# OBCv4_22.net
KiCad netlist of a schematic drawn in EAGLE
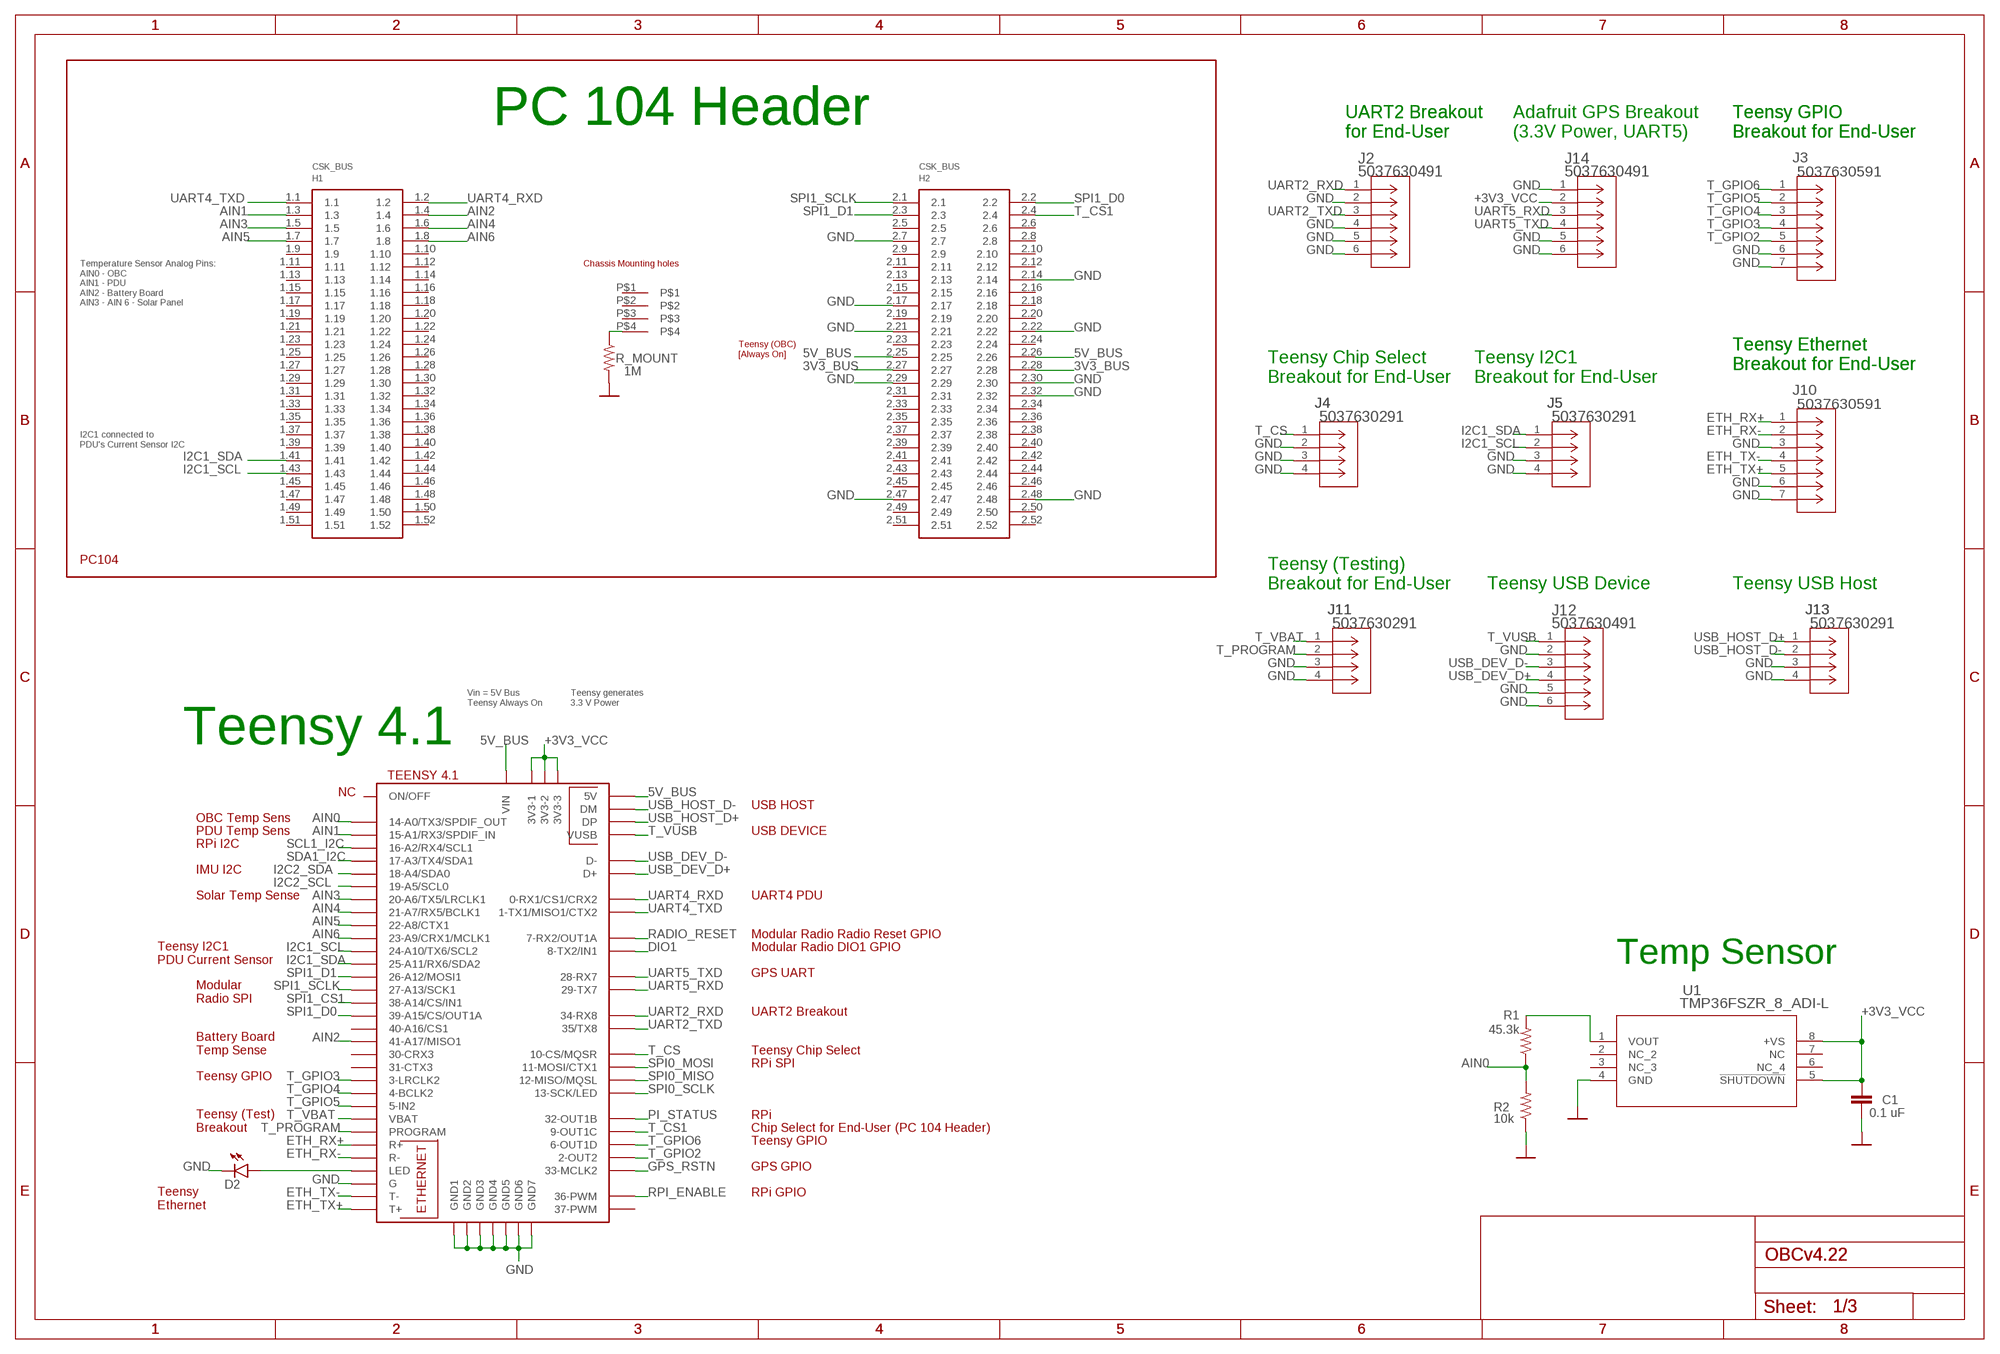
[diagram p0: schematic, sheet 1]
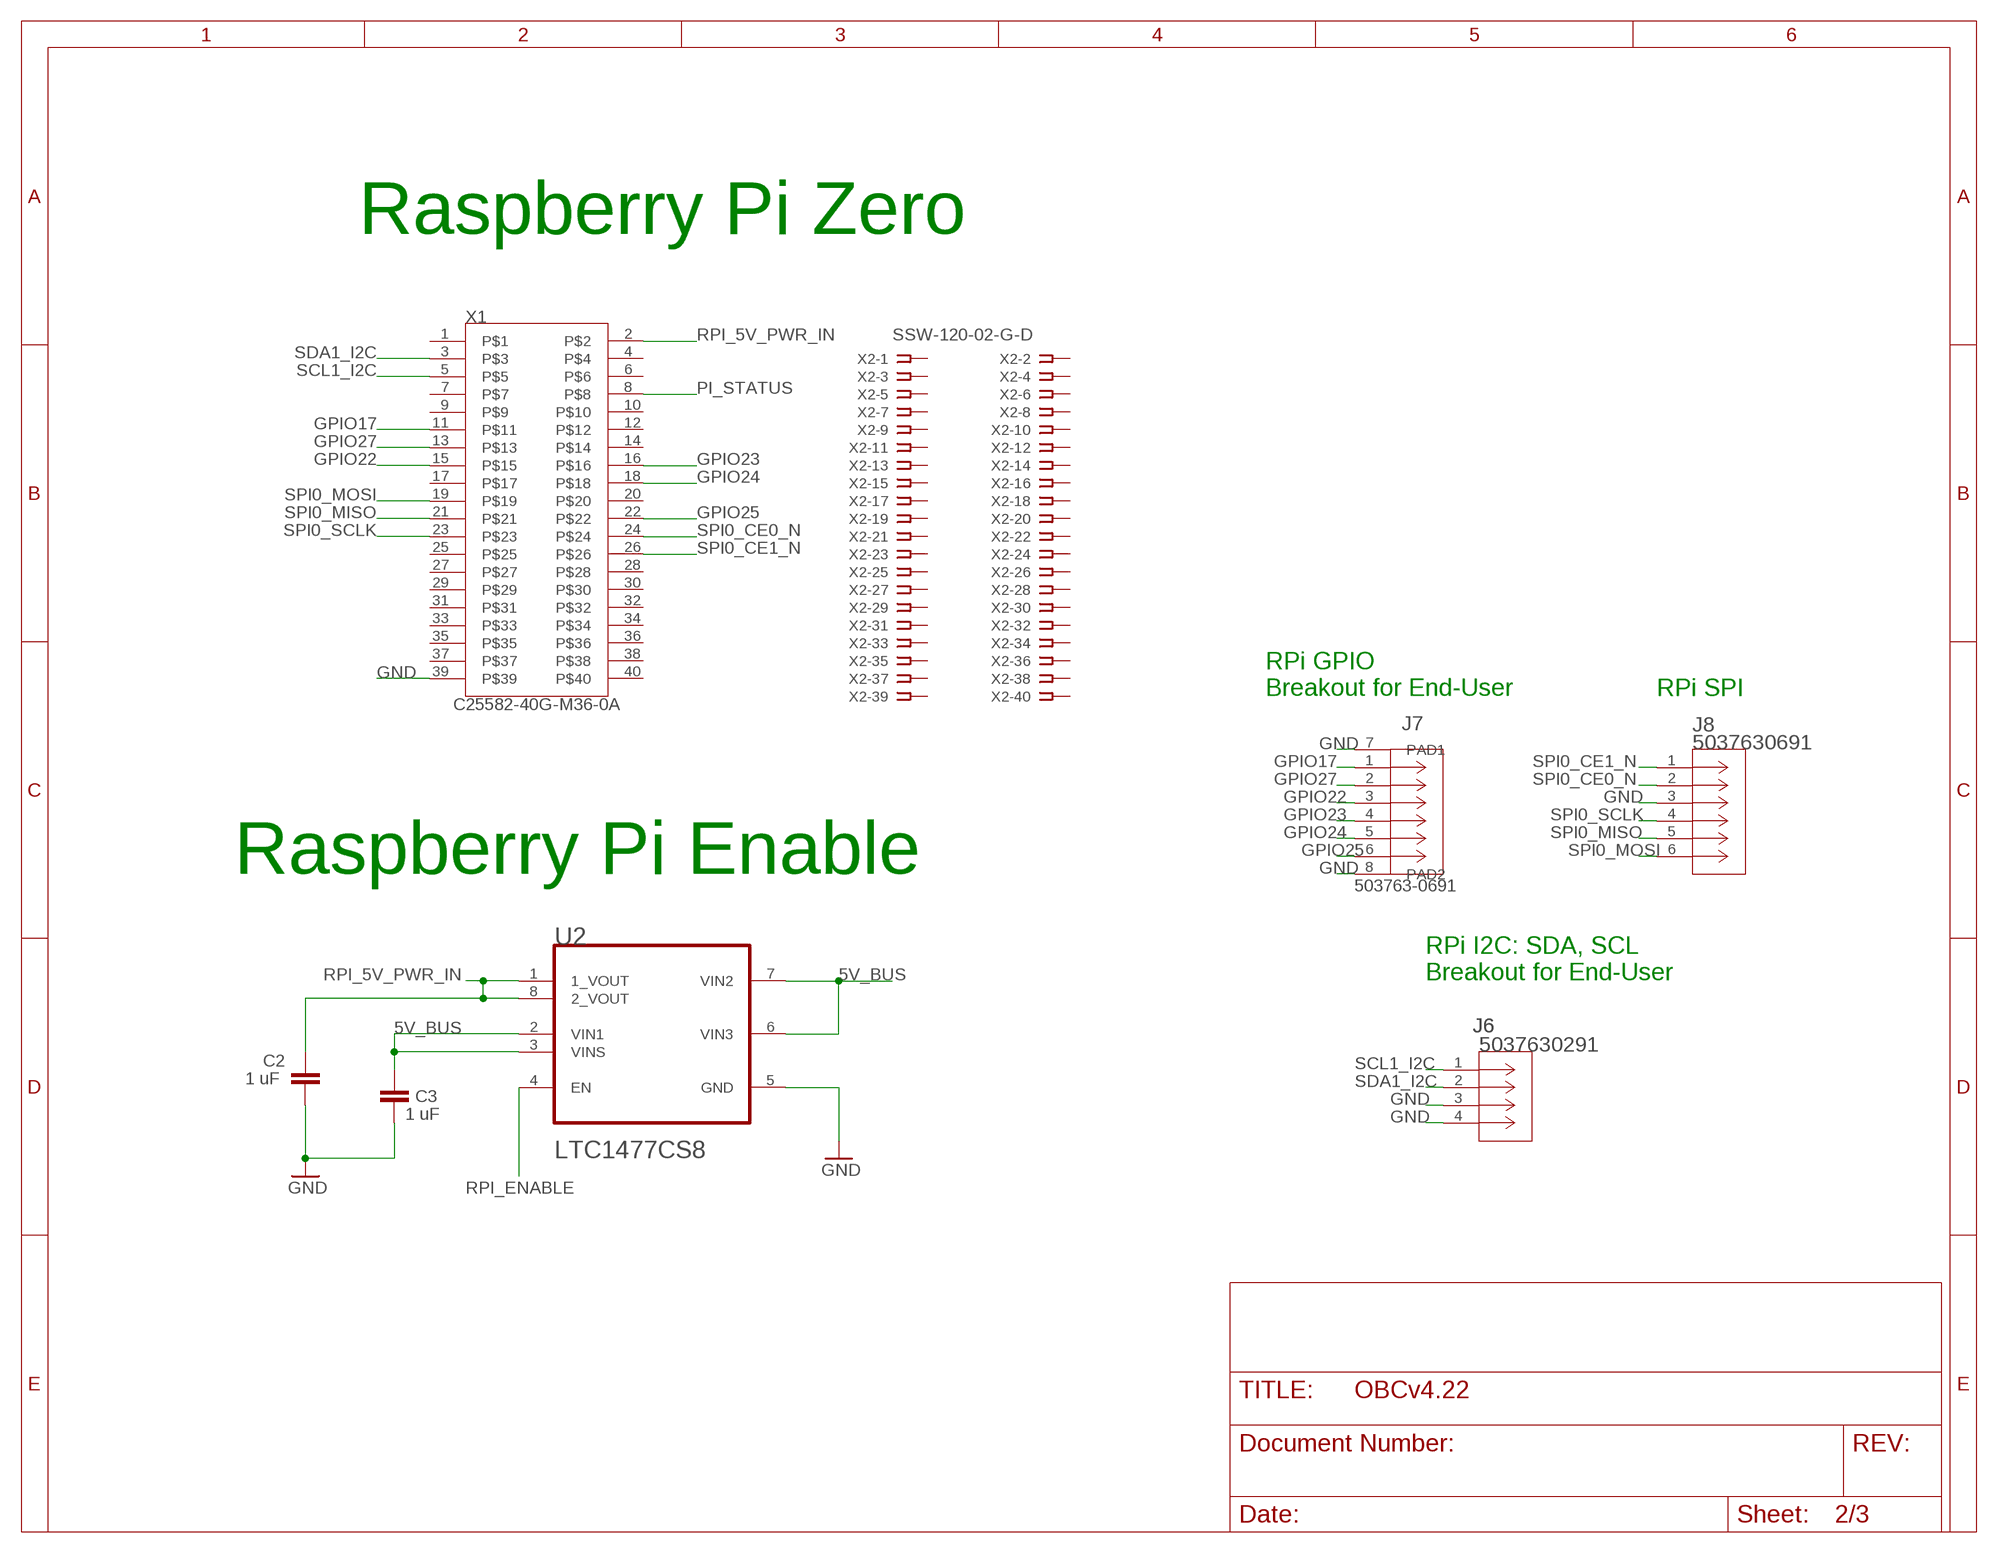
[diagram p1: schematic, sheet 2]
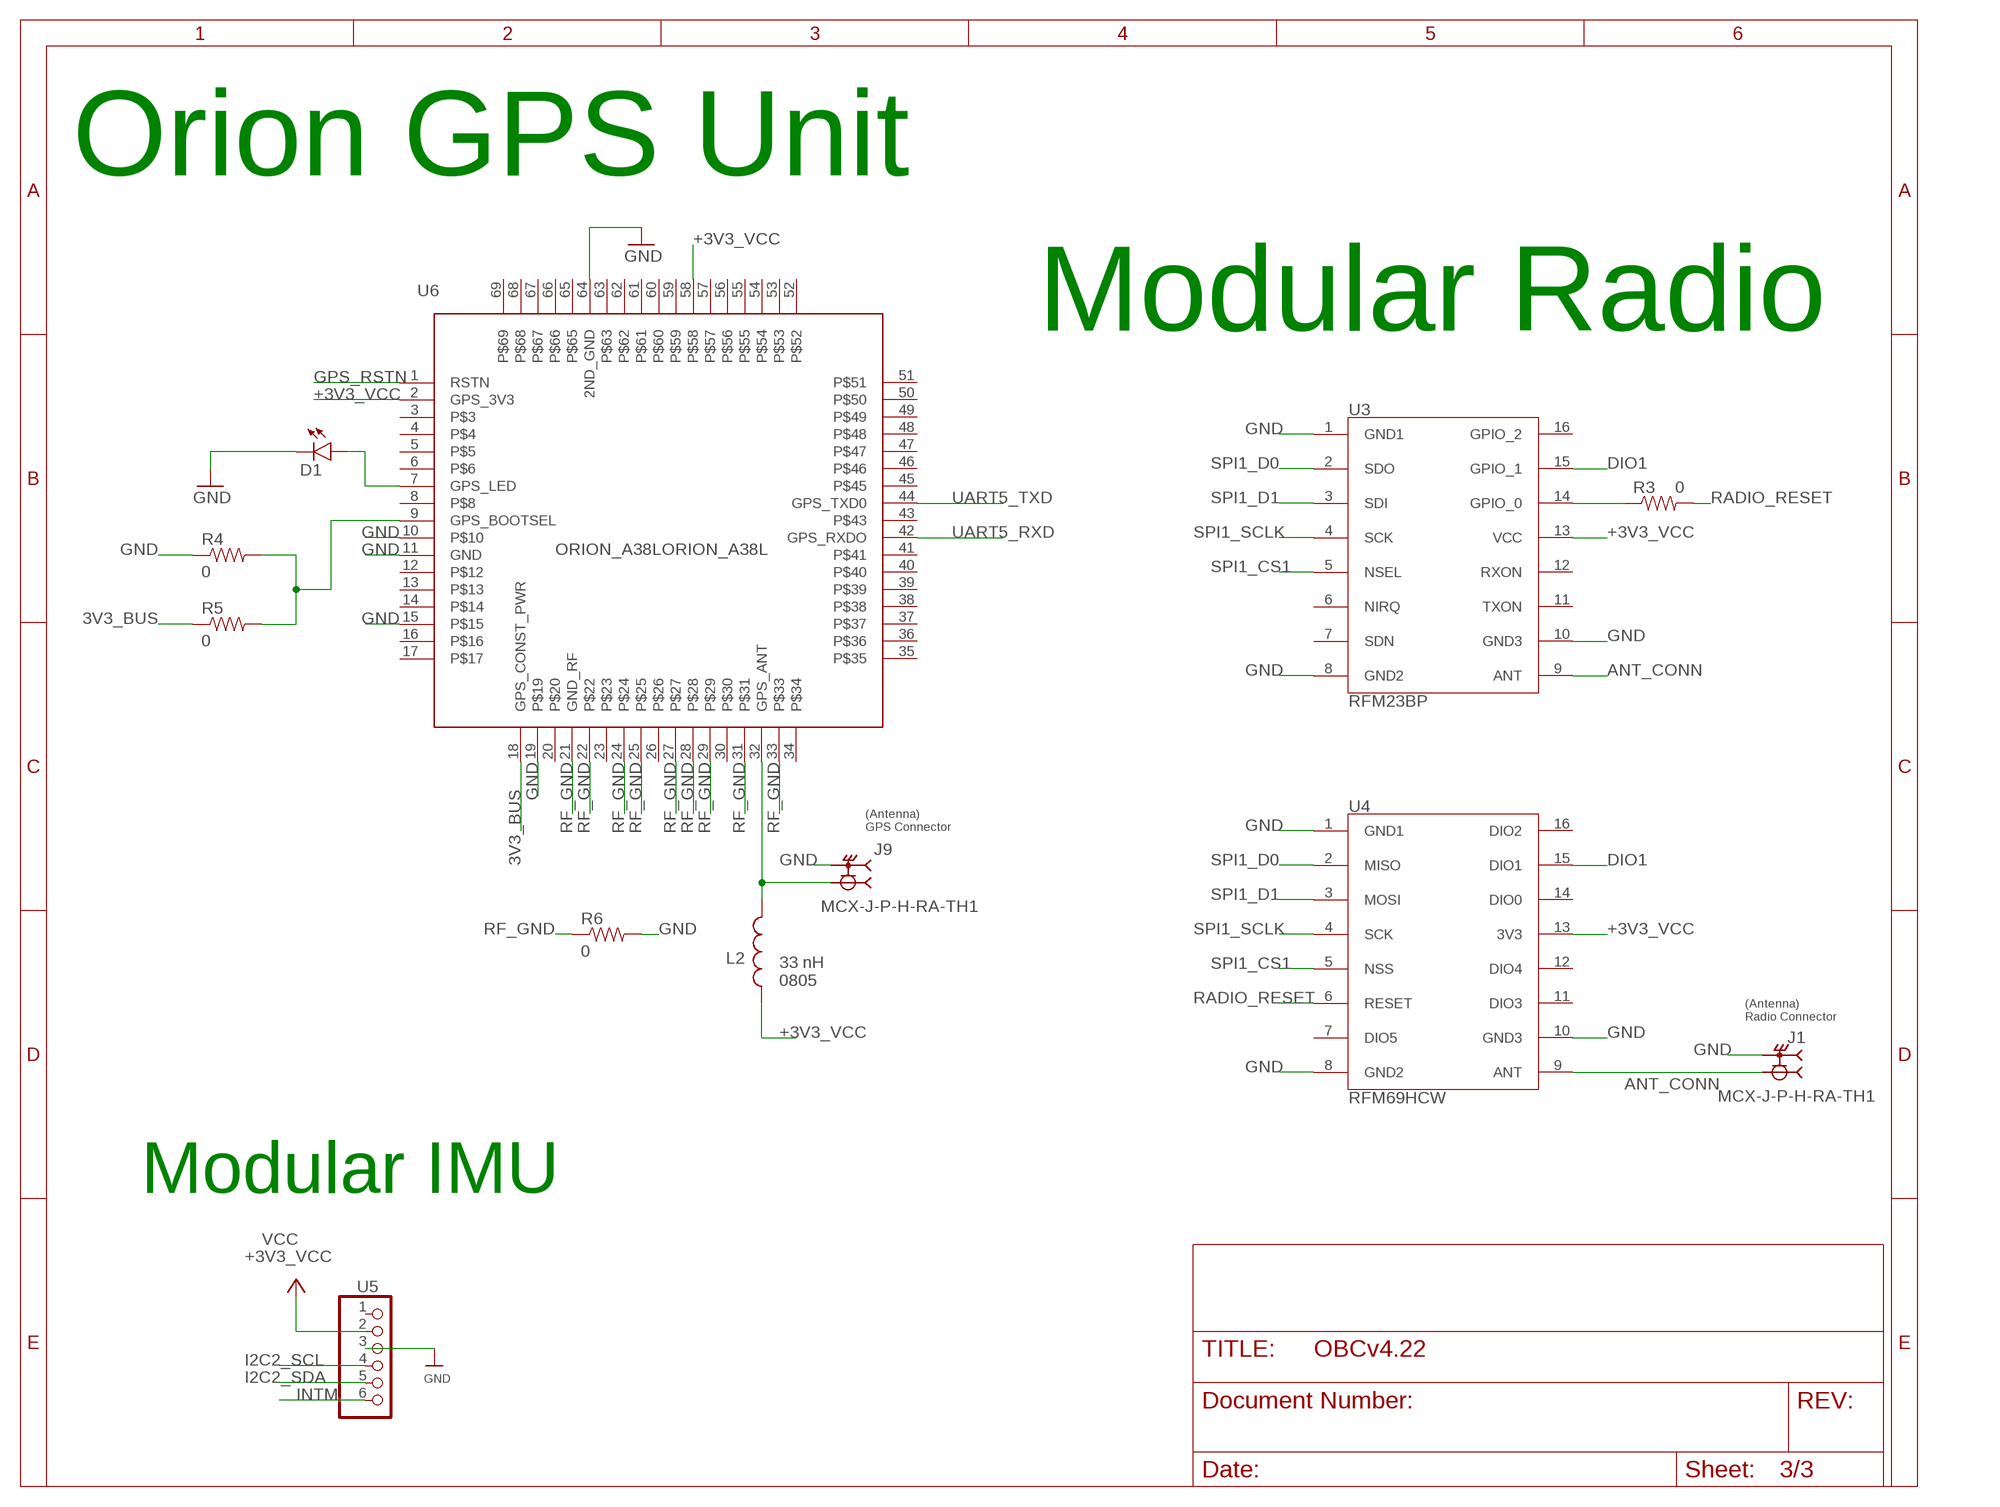
[diagram p2: schematic, sheet 3]

(export (version "E")
  (design (tool "Eeschema 10.0.6"))
  (components
    (comp (ref "C2")
      (value "1 uF")
      (footprint "eagle-import:0805")
      (libsource (lib "eagle-import") (part "CAP0805"))
    )
    (comp (ref "C3")
      (value "1 uF")
      (footprint "eagle-import:0805")
      (libsource (lib "eagle-import") (part "CAP0805"))
    )
    (comp (ref "J6")
      (value "5037630291")
      (footprint "eagle-import:CON_5037630291")
      (fields (field (name "COPYRIGHT") "Copyright (C) 2018 Accelerated Designs. All rights reserved"))
      (libsource (lib "eagle-import") (part "5037630291"))
    )
    (comp (ref "J7")
      (value "503763-0691")
      (footprint "eagle-import:CONN_503763-0691_MOL")
      (fields (field (name "COPYRIGHT") "Copyright (C) 2018 Accelerated Designs. All rights reserved"))
      (libsource (lib "eagle-import") (part "503763-0691"))
    )
    (comp (ref "J8")
      (value "5037630691")
      (footprint "eagle-import:CONN_503763-0691_MOL")
      (fields
        (field (name "MANUFACTURER_PART_NUMBER") "503763-0691")
        (field (name "COPYRIGHT") "Copyright (C) 2018 Accelerated Designs. All rights reserved")
      )
      (libsource (lib "eagle-import") (part "5037630691"))
    )
    (comp (ref "U2")
      (value "LTC1477CS8LINEAR_TECHNOLOGY_LTC1477CS8_0_2")
      (footprint "eagle-import:LINEAR_TECHNOLOGY_LTC1477CS8_2")
      (fields (field (name "MF") "Linear Technology") (field (name "MPN") "LTC1477CS8"))
      (libsource (lib "eagle-import") (part "LTC1477CS8LINEAR_TECHNOLOGY_LTC1477CS8_0_2"))
    )
    (comp (ref "X1")
      (value "C25582-40G-M36-0A")
      (footprint "eagle-import:ADAFRUIT_C25582-40G-M36-0A_0")
      (libsource (lib "eagle-import") (part "C25582-40G-M36-0A"))
    )
    (comp (ref "X2")
      (value "SSW-120-02-G-D")
      (footprint "eagle-import:SSW-120-02-G-D")
      (fields (field (name "MF") "Samtec Inc."))
      (libsource (lib "eagle-import") (part "SSW-120-02-G-D"))
    )
    (comp (ref "D1")
      (value "LEDCHIP-LED0603")
      (footprint "eagle-import:CHIP-LED0603")
      (libsource (lib "eagle-import") (part "LEDCHIP-LED0603"))
    )
    (comp (ref "J1")
      (value "MCX-J-P-H-RA-TH1")
      (footprint "eagle-import:SAMTEC_MCX-J-P-H-RA-TH1")
      (fields (field (name "DIGI-KEY_PART_NUMBER") "SAM10607-ND") (field (name "MF") "Samtec"))
      (libsource (lib "eagle-import") (part "MCX-J-P-H-RA-TH1"))
    )
    (comp (ref "J9")
      (value "MCX-J-P-H-RA-TH1")
      (footprint "eagle-import:SAMTEC_MCX-J-P-H-RA-TH1")
      (fields (field (name "DIGI-KEY_PART_NUMBER") "SAM10607-ND") (field (name "MF") "Samtec"))
      (libsource (lib "eagle-import") (part "MCX-J-P-H-RA-TH1"))
    )
    (comp (ref "L2")
      (value "AIMC-0805-2N2S-T")
      (footprint "eagle-import:INDC2012X105N")
      (fields (field (name "DIGI-KEY_PART_NUMBER") "535-11562-1-ND") (field (name "MF") "Abracon"))
      (libsource (lib "eagle-import") (part "AIMC-0805-2N2S-T"))
    )
    (comp (ref "R3")
      (value "0")
      (footprint "eagle-import:0805")
      (libsource (lib "eagle-import") (part "RESISTOR0805-RES"))
    )
    (comp (ref "R4")
      (value "0")
      (footprint "eagle-import:0805")
      (libsource (lib "eagle-import") (part "RESISTOR0805-RES"))
    )
    (comp (ref "R5")
      (value "0")
      (footprint "eagle-import:0805")
      (libsource (lib "eagle-import") (part "RESISTOR0805-RES"))
    )
    (comp (ref "R6")
      (value "0")
      (footprint "eagle-import:0805")
      (libsource (lib "eagle-import") (part "RESISTOR0805-RES"))
    )
    (comp (ref "U3")
      (value "RFM23BP")
      (footprint "eagle-import:RFM23BP")
      (libsource (lib "eagle-import") (part "RFM23BP"))
    )
    (comp (ref "U4")
      (value "RFM69HCW")
      (footprint "eagle-import:RFM69HCW")
      (libsource (lib "eagle-import") (part "RFM69HCW"))
    )
    (comp (ref "U5")
      (value "HEADER-1X670MIL")
      (footprint "eagle-import:1X06_ROUND_70")
      (libsource (lib "eagle-import") (part "HEADER-1X670MIL"))
    )
    (comp (ref "U6")
      (value "ORION_A38LORION_A38L")
      (footprint "eagle-import:ORION_A38L")
      (libsource (lib "eagle-import") (part "ORION_A38LORION_A38L"))
    )
    (comp (ref "C1")
      (value "0.1 uF")
      (footprint "eagle-import:0805")
      (libsource (lib "eagle-import") (part "CAP0805"))
    )
    (comp (ref "D2")
      (value "LEDCHIP-LED0603")
      (footprint "eagle-import:CHIP-LED0603")
      (libsource (lib "eagle-import") (part "LEDCHIP-LED0603"))
    )
    (comp (ref "H1")
      (value "PC104_WCONN")
      (footprint "eagle-import:PC104_WCONN")
      (libsource (lib "eagle-import") (part "PC104_WCONN"))
    )
    (comp (ref "J2")
      (value "5037630491")
      (footprint "eagle-import:CON_5037630491")
      (fields (field (name "COPYRIGHT") "Copyright (C) 2018 Accelerated Designs. All rights reserved"))
      (libsource (lib "eagle-import") (part "5037630491"))
    )
    (comp (ref "J3")
      (value "5037630591")
      (footprint "eagle-import:CON_5037630591")
      (fields (field (name "COPYRIGHT") "Copyright (C) 2021 Ultra Librarian. All rights reserved."))
      (libsource (lib "eagle-import") (part "5037630591"))
    )
    (comp (ref "J4")
      (value "5037630291")
      (footprint "eagle-import:CON_5037630291")
      (fields (field (name "COPYRIGHT") "Copyright (C) 2018 Accelerated Designs. All rights reserved"))
      (libsource (lib "eagle-import") (part "5037630291"))
    )
    (comp (ref "J5")
      (value "5037630291")
      (footprint "eagle-import:CON_5037630291")
      (fields (field (name "COPYRIGHT") "Copyright (C) 2018 Accelerated Designs. All rights reserved"))
      (libsource (lib "eagle-import") (part "5037630291"))
    )
    (comp (ref "J10")
      (value "5037630591")
      (footprint "eagle-import:CON_5037630591")
      (fields (field (name "COPYRIGHT") "Copyright (C) 2021 Ultra Librarian. All rights reserved."))
      (libsource (lib "eagle-import") (part "5037630591"))
    )
    (comp (ref "J11")
      (value "5037630291")
      (footprint "eagle-import:CON_5037630291")
      (fields (field (name "COPYRIGHT") "Copyright (C) 2018 Accelerated Designs. All rights reserved"))
      (libsource (lib "eagle-import") (part "5037630291"))
    )
    (comp (ref "J12")
      (value "5037630491")
      (footprint "eagle-import:CON_5037630491")
      (fields (field (name "COPYRIGHT") "Copyright (C) 2018 Accelerated Designs. All rights reserved"))
      (libsource (lib "eagle-import") (part "5037630491"))
    )
    (comp (ref "J13")
      (value "5037630291")
      (footprint "eagle-import:CON_5037630291")
      (fields (field (name "COPYRIGHT") "Copyright (C) 2018 Accelerated Designs. All rights reserved"))
      (libsource (lib "eagle-import") (part "5037630291"))
    )
    (comp (ref "J14")
      (value "5037630491")
      (footprint "eagle-import:CON_5037630491")
      (fields (field (name "COPYRIGHT") "Copyright (C) 2018 Accelerated Designs. All rights reserved"))
      (libsource (lib "eagle-import") (part "5037630491"))
    )
    (comp (ref "R1")
      (value "45.3k")
      (footprint "eagle-import:0805")
      (libsource (lib "eagle-import") (part "RESISTOR0805-RES"))
    )
    (comp (ref "R2")
      (value "10k")
      (footprint "eagle-import:0805")
      (libsource (lib "eagle-import") (part "RESISTOR0805-RES"))
    )
    (comp (ref "R_MOUNT")
      (value "1M")
      (footprint "eagle-import:0805")
      (libsource (lib "eagle-import") (part "RESISTOR0805-RES"))
    )
    (comp (ref "U$1")
      (value "TEENSY41TEENSY")
      (footprint "eagle-import:TEENSY41")
      (libsource (lib "eagle-import") (part "TEENSY41TEENSY"))
    )
    (comp (ref "U1")
      (value "TMP36FSZR_8_ADI-L")
      (footprint "eagle-import:R_8_ADI-L")
      (fields
        (field (name "MANUFACTURER_PART_NUMBER") "TMP36FSZ")
        (field (name "COPYRIGHT") "Copyright (C) 2021 Ultra Librarian. All rights reserved.")
      )
      (libsource (lib "eagle-import") (part "TMP36FSZR_8_ADI-L"))
    )
  )
  (nets
    (net (code "1") (name "+3V3_VCC") (class "Default")
      (node (ref "C1") (pin "1") (pinfunction "1_1") (pintype "passive"))
      (node (ref "J14") (pin "2") (pinfunction "2_2") (pintype "passive"))
      (node (ref "L2") (pin "1") (pinfunction "1_1") (pintype "passive"))
      (node (ref "U$1") (pin "3V3-1") (pinfunction "3V3-1_3V3-1") (pintype "bidirectional"))
      (node (ref "U$1") (pin "3V3-2") (pinfunction "3V3-2_3V3-2") (pintype "bidirectional"))
      (node (ref "U$1") (pin "3V3-3") (pinfunction "3V3-3_3V3-3") (pintype "bidirectional"))
      (node (ref "U1") (pin "5") (pinfunction "~{SHUTDOWN}_5") (pintype "passive"))
      (node (ref "U1") (pin "8") (pinfunction "+VS_8") (pintype "power_in"))
      (node (ref "U3") (pin "13") (pinfunction "VCC_13") (pintype "bidirectional"))
      (node (ref "U4") (pin "13") (pinfunction "3V3_13") (pintype "bidirectional"))
      (node (ref "U5") (pin "2") (pinfunction "2_2") (pintype "passive"))
      (node (ref "U6") (pin "2") (pinfunction "GPS_3V3_2") (pintype "bidirectional"))
      (node (ref "U6") (pin "58") (pinfunction "P$58_58") (pintype "bidirectional"))
    )
    (net (code "2") (name "3V3_BUS") (class "Default")
      (node (ref "H1") (pin "2.27") (pinfunction "2.27_2.27") (pintype "bidirectional"))
      (node (ref "H1") (pin "2.28") (pinfunction "2.28_2.28") (pintype "bidirectional"))
      (node (ref "R5") (pin "1") (pinfunction "1_1") (pintype "passive"))
      (node (ref "U6") (pin "18") (pinfunction "GPS_CONST_PWR_18") (pintype "bidirectional"))
    )
    (net (code "3") (name "5V_BUS") (class "Default")
      (node (ref "C3") (pin "1") (pinfunction "1_1") (pintype "passive"))
      (node (ref "H1") (pin "2.25") (pinfunction "2.25_2.25") (pintype "bidirectional"))
      (node (ref "H1") (pin "2.26") (pinfunction "2.26_2.26") (pintype "bidirectional"))
      (node (ref "U$1") (pin "+5V") (pinfunction "5V_+5V") (pintype "bidirectional"))
      (node (ref "U$1") (pin "VIN") (pinfunction "VIN_VIN") (pintype "bidirectional"))
      (node (ref "U2") (pin "2") (pinfunction "VIN1_2") (pintype "power_in"))
      (node (ref "U2") (pin "3") (pinfunction "VINS_3") (pintype "power_in"))
      (node (ref "U2") (pin "6") (pinfunction "VIN3_6") (pintype "power_in"))
      (node (ref "U2") (pin "7") (pinfunction "VIN2_7") (pintype "power_in"))
    )
    (net (code "4") (name "AIN0") (class "Default")
      (node (ref "R1") (pin "1") (pinfunction "1_1") (pintype "passive"))
      (node (ref "R2") (pin "2") (pinfunction "2_2") (pintype "passive"))
      (node (ref "U$1") (pin "14-A0/TX3/SPDIF_OUT") (pinfunction "14-A0/TX3/SPDIF_OUT_14-A0/TX3/SPDIF_OUT") (pintype "bidirectional"))
    )
    (net (code "5") (name "AIN1") (class "Default")
      (node (ref "H1") (pin "1.3") (pinfunction "1.3_1.3") (pintype "bidirectional"))
      (node (ref "U$1") (pin "15-A1/RX3/SPDIF_IN") (pinfunction "15-A1/RX3/SPDIF_IN_15-A1/RX3/SPDIF_IN") (pintype "bidirectional"))
    )
    (net (code "6") (name "AIN2") (class "Default")
      (node (ref "H1") (pin "1.4") (pinfunction "1.4_1.4") (pintype "bidirectional"))
      (node (ref "U$1") (pin "41-A17/MISO1") (pinfunction "41-A17/MISO1_41-A17/MISO1") (pintype "bidirectional"))
    )
    (net (code "7") (name "AIN3") (class "Default")
      (node (ref "H1") (pin "1.5") (pinfunction "1.5_1.5") (pintype "bidirectional"))
      (node (ref "U$1") (pin "20-A6/TX5/LRCLK1") (pinfunction "20-A6/TX5/LRCLK1_20-A6/TX5/LRCLK1") (pintype "bidirectional"))
    )
    (net (code "8") (name "AIN4") (class "Default")
      (node (ref "H1") (pin "1.6") (pinfunction "1.6_1.6") (pintype "bidirectional"))
      (node (ref "U$1") (pin "21-A7/RX5/BCLK1") (pinfunction "21-A7/RX5/BCLK1_21-A7/RX5/BCLK1") (pintype "bidirectional"))
    )
    (net (code "9") (name "AIN5") (class "Default")
      (node (ref "H1") (pin "1.7") (pinfunction "1.7_1.7") (pintype "bidirectional"))
      (node (ref "U$1") (pin "22-A8/CTX1") (pinfunction "22-A8/CTX1_22-A8/CTX1") (pintype "bidirectional"))
    )
    (net (code "10") (name "AIN6") (class "Default")
      (node (ref "H1") (pin "1.8") (pinfunction "1.8_1.8") (pintype "bidirectional"))
      (node (ref "U$1") (pin "23-A9/CRX1/MCLK1") (pinfunction "23-A9/CRX1/MCLK1_23-A9/CRX1/MCLK1") (pintype "bidirectional"))
    )
    (net (code "11") (name "ANT_CONN") (class "Default")
      (node (ref "J1") (pin "1") (pinfunction "1_1") (pintype "passive"))
      (node (ref "U3") (pin "9") (pinfunction "ANT_9") (pintype "bidirectional"))
      (node (ref "U4") (pin "9") (pinfunction "ANT_9") (pintype "bidirectional"))
    )
    (net (code "12") (name "DIO1") (class "Default")
      (node (ref "U$1") (pin "8-TX2/IN1") (pinfunction "8-TX2/IN1_8-TX2/IN1") (pintype "bidirectional"))
      (node (ref "U3") (pin "15") (pinfunction "GPIO_1_15") (pintype "bidirectional"))
      (node (ref "U4") (pin "15") (pinfunction "DIO1_15") (pintype "bidirectional"))
    )
    (net (code "13") (name "ETH_RX+") (class "Default")
      (node (ref "J10") (pin "1") (pinfunction "1_1") (pintype "passive"))
      (node (ref "U$1") (pin "R+") (pinfunction "R+_R+") (pintype "bidirectional"))
    )
    (net (code "14") (name "ETH_RX-") (class "Default")
      (node (ref "J10") (pin "2") (pinfunction "2_2") (pintype "passive"))
      (node (ref "U$1") (pin "R-") (pinfunction "R-_R-") (pintype "bidirectional"))
    )
    (net (code "15") (name "ETH_TX+") (class "Default")
      (node (ref "J10") (pin "5") (pinfunction "5_5") (pintype "passive"))
      (node (ref "U$1") (pin "T+") (pinfunction "T+_T+") (pintype "bidirectional"))
    )
    (net (code "16") (name "ETH_TX-") (class "Default")
      (node (ref "J10") (pin "4") (pinfunction "4_4") (pintype "passive"))
      (node (ref "U$1") (pin "T-") (pinfunction "T-_T-") (pintype "bidirectional"))
    )
    (net (code "17") (name "GND") (class "Default")
      (node (ref "C1") (pin "2") (pinfunction "2_2") (pintype "passive"))
      (node (ref "C2") (pin "2") (pinfunction "2_2") (pintype "passive"))
      (node (ref "C3") (pin "2") (pinfunction "2_2") (pintype "passive"))
      (node (ref "D1") (pin "C") (pinfunction "C_C") (pintype "passive"))
      (node (ref "D2") (pin "C") (pinfunction "C_C") (pintype "passive"))
      (node (ref "H1") (pin "2.14") (pinfunction "2.14_2.14") (pintype "bidirectional"))
      (node (ref "H1") (pin "2.17") (pinfunction "2.17_2.17") (pintype "bidirectional"))
      (node (ref "H1") (pin "2.21") (pinfunction "2.21_2.21") (pintype "bidirectional"))
      (node (ref "H1") (pin "2.22") (pinfunction "2.22_2.22") (pintype "bidirectional"))
      (node (ref "H1") (pin "2.29") (pinfunction "2.29_2.29") (pintype "bidirectional"))
      (node (ref "H1") (pin "2.30") (pinfunction "2.30_2.30") (pintype "bidirectional"))
      (node (ref "H1") (pin "2.32") (pinfunction "2.32_2.32") (pintype "bidirectional"))
      (node (ref "H1") (pin "2.47") (pinfunction "2.47_2.47") (pintype "bidirectional"))
      (node (ref "H1") (pin "2.48") (pinfunction "2.48_2.48") (pintype "bidirectional"))
      (node (ref "H1") (pin "2.7") (pinfunction "2.7_2.7") (pintype "bidirectional"))
      (node (ref "J1") (pin "S1") (pinfunction "2_S1") (pintype "passive"))
      (node (ref "J1") (pin "S2") (pinfunction "2_S2") (pintype "passive"))
      (node (ref "J1") (pin "S3") (pinfunction "2_S3") (pintype "passive"))
      (node (ref "J1") (pin "S4") (pinfunction "2_S4") (pintype "passive"))
      (node (ref "J10") (pin "3") (pinfunction "3_3") (pintype "passive"))
      (node (ref "J10") (pin "6") (pinfunction "6_6") (pintype "passive"))
      (node (ref "J10") (pin "7") (pinfunction "7_7") (pintype "passive"))
      (node (ref "J11") (pin "3") (pinfunction "3_3") (pintype "passive"))
      (node (ref "J11") (pin "4") (pinfunction "4_4") (pintype "passive"))
      (node (ref "J12") (pin "2") (pinfunction "2_2") (pintype "passive"))
      (node (ref "J12") (pin "5") (pinfunction "5_5") (pintype "passive"))
      (node (ref "J12") (pin "6") (pinfunction "6_6") (pintype "passive"))
      (node (ref "J13") (pin "3") (pinfunction "3_3") (pintype "passive"))
      (node (ref "J13") (pin "4") (pinfunction "4_4") (pintype "passive"))
      (node (ref "J14") (pin "1") (pinfunction "1_1") (pintype "passive"))
      (node (ref "J14") (pin "5") (pinfunction "5_5") (pintype "passive"))
      (node (ref "J14") (pin "6") (pinfunction "6_6") (pintype "passive"))
      (node (ref "J2") (pin "2") (pinfunction "2_2") (pintype "passive"))
      (node (ref "J2") (pin "4") (pinfunction "4_4") (pintype "passive"))
      (node (ref "J2") (pin "5") (pinfunction "5_5") (pintype "passive"))
      (node (ref "J2") (pin "6") (pinfunction "6_6") (pintype "passive"))
      (node (ref "J3") (pin "6") (pinfunction "6_6") (pintype "passive"))
      (node (ref "J3") (pin "7") (pinfunction "7_7") (pintype "passive"))
      (node (ref "J4") (pin "2") (pinfunction "2_2") (pintype "passive"))
      (node (ref "J4") (pin "3") (pinfunction "3_3") (pintype "passive"))
      (node (ref "J4") (pin "4") (pinfunction "4_4") (pintype "passive"))
      (node (ref "J5") (pin "3") (pinfunction "3_3") (pintype "passive"))
      (node (ref "J5") (pin "4") (pinfunction "4_4") (pintype "passive"))
      (node (ref "J6") (pin "3") (pinfunction "3_3") (pintype "passive"))
      (node (ref "J6") (pin "4") (pinfunction "4_4") (pintype "passive"))
      (node (ref "J7") (pin "7") (pinfunction "PAD1_7") (pintype "bidirectional"))
      (node (ref "J7") (pin "8") (pinfunction "PAD2_8") (pintype "bidirectional"))
      (node (ref "J8") (pin "3") (pinfunction "3_3") (pintype "passive"))
      (node (ref "J9") (pin "S1") (pinfunction "2_S1") (pintype "passive"))
      (node (ref "J9") (pin "S2") (pinfunction "2_S2") (pintype "passive"))
      (node (ref "J9") (pin "S3") (pinfunction "2_S3") (pintype "passive"))
      (node (ref "J9") (pin "S4") (pinfunction "2_S4") (pintype "passive"))
      (node (ref "R2") (pin "1") (pinfunction "1_1") (pintype "passive"))
      (node (ref "R4") (pin "1") (pinfunction "1_1") (pintype "passive"))
      (node (ref "R6") (pin "2") (pinfunction "2_2") (pintype "passive"))
      (node (ref "R_MOUNT") (pin "2") (pinfunction "2_2") (pintype "passive"))
      (node (ref "U$1") (pin "G") (pinfunction "G_G") (pintype "bidirectional"))
      (node (ref "U$1") (pin "GND") (pinfunction "GND7_GND") (pintype "bidirectional"))
      (node (ref "U$1") (pin "GND1") (pinfunction "GND1_GND1") (pintype "bidirectional"))
      (node (ref "U$1") (pin "GND2") (pinfunction "GND2_GND2") (pintype "bidirectional"))
      (node (ref "U$1") (pin "GND3") (pinfunction "GND3_GND3") (pintype "bidirectional"))
      (node (ref "U$1") (pin "GND4") (pinfunction "GND4_GND4") (pintype "bidirectional"))
      (node (ref "U$1") (pin "GND5") (pinfunction "GND5_GND5") (pintype "bidirectional"))
      (node (ref "U$1") (pin "GND6") (pinfunction "GND6_GND6") (pintype "bidirectional"))
      (node (ref "U1") (pin "4") (pinfunction "GND_4") (pintype "passive"))
      (node (ref "U2") (pin "5") (pinfunction "GND_5") (pintype "power_in"))
      (node (ref "U3") (pin "1") (pinfunction "GND1_1") (pintype "bidirectional"))
      (node (ref "U3") (pin "10") (pinfunction "GND3_10") (pintype "bidirectional"))
      (node (ref "U3") (pin "8") (pinfunction "GND2_8") (pintype "bidirectional"))
      (node (ref "U4") (pin "1") (pinfunction "GND1_1") (pintype "bidirectional"))
      (node (ref "U4") (pin "10") (pinfunction "GND3_10") (pintype "bidirectional"))
      (node (ref "U4") (pin "8") (pinfunction "GND2_8") (pintype "bidirectional"))
      (node (ref "U5") (pin "3") (pinfunction "3_3") (pintype "passive"))
      (node (ref "U6") (pin "10") (pinfunction "P$10_10") (pintype "bidirectional"))
      (node (ref "U6") (pin "11") (pinfunction "GND_11") (pintype "bidirectional"))
      (node (ref "U6") (pin "15") (pinfunction "P$15_15") (pintype "bidirectional"))
      (node (ref "U6") (pin "19") (pinfunction "P$19_19") (pintype "bidirectional"))
      (node (ref "U6") (pin "64") (pinfunction "2ND_GND_64") (pintype "bidirectional"))
      (node (ref "X1") (pin "39") (pinfunction "P$39_39") (pintype "bidirectional"))
    )
    (net (code "18") (name "GPIO17") (class "Default")
      (node (ref "J7") (pin "1") (pinfunction "1_1") (pintype "passive"))
      (node (ref "X1") (pin "11") (pinfunction "P$11_11") (pintype "bidirectional"))
    )
    (net (code "19") (name "GPIO22") (class "Default")
      (node (ref "J7") (pin "3") (pinfunction "3_3") (pintype "passive"))
      (node (ref "X1") (pin "15") (pinfunction "P$15_15") (pintype "bidirectional"))
    )
    (net (code "20") (name "GPIO23") (class "Default")
      (node (ref "J7") (pin "4") (pinfunction "4_4") (pintype "passive"))
      (node (ref "X1") (pin "16") (pinfunction "P$16_16") (pintype "bidirectional"))
    )
    (net (code "21") (name "GPIO24") (class "Default")
      (node (ref "J7") (pin "5") (pinfunction "5_5") (pintype "passive"))
      (node (ref "X1") (pin "18") (pinfunction "P$18_18") (pintype "bidirectional"))
    )
    (net (code "22") (name "GPIO25") (class "Default")
      (node (ref "J7") (pin "6") (pinfunction "6_6") (pintype "passive"))
      (node (ref "X1") (pin "22") (pinfunction "P$22_22") (pintype "bidirectional"))
    )
    (net (code "23") (name "GPIO27") (class "Default")
      (node (ref "J7") (pin "2") (pinfunction "2_2") (pintype "passive"))
      (node (ref "X1") (pin "13") (pinfunction "P$13_13") (pintype "bidirectional"))
    )
    (net (code "24") (name "GPS_RSTN") (class "Default")
      (node (ref "U$1") (pin "33-MCLK2") (pinfunction "33-MCLK2_33-MCLK2") (pintype "bidirectional"))
      (node (ref "U6") (pin "1") (pinfunction "RSTN_1") (pintype "bidirectional"))
    )
    (net (code "25") (name "I2C1_SCL") (class "Default")
      (node (ref "H1") (pin "1.43") (pinfunction "1.43_1.43") (pintype "bidirectional"))
      (node (ref "J5") (pin "2") (pinfunction "2_2") (pintype "passive"))
      (node (ref "U$1") (pin "24-A10/TX6/SCL2") (pinfunction "24-A10/TX6/SCL2_24-A10/TX6/SCL2") (pintype "bidirectional"))
    )
    (net (code "26") (name "I2C1_SDA") (class "Default")
      (node (ref "H1") (pin "1.41") (pinfunction "1.41_1.41") (pintype "bidirectional"))
      (node (ref "J5") (pin "1") (pinfunction "1_1") (pintype "passive"))
      (node (ref "U$1") (pin "25-A11/RX6/SDA2") (pinfunction "25-A11/RX6/SDA2_25-A11/RX6/SDA2") (pintype "bidirectional"))
    )
    (net (code "27") (name "I2C2_SCL") (class "Default")
      (node (ref "U$1") (pin "19-A5/SCL0") (pinfunction "19-A5/SCL0_19-A5/SCL0") (pintype "bidirectional"))
      (node (ref "U5") (pin "4") (pinfunction "4_4") (pintype "passive"))
    )
    (net (code "28") (name "I2C2_SDA") (class "Default")
      (node (ref "U$1") (pin "18-A4/SDA0") (pinfunction "18-A4/SDA0_18-A4/SDA0") (pintype "bidirectional"))
      (node (ref "U5") (pin "5") (pinfunction "5_5") (pintype "passive"))
    )
    (net (code "29") (name "INTM") (class "Default")
      (node (ref "U5") (pin "6") (pinfunction "6_6") (pintype "passive"))
    )
    (net (code "30") (name "Net-(D2-PadA)") (class "Default")
      (node (ref "D2") (pin "A") (pinfunction "A_A") (pintype "passive"))
      (node (ref "U$1") (pin "LED") (pinfunction "LED_LED") (pintype "bidirectional"))
    )
    (net (code "31") (name "Net-(H1-PadP$4)") (class "Default")
      (node (ref "H1") (pin "P$4") (pinfunction "P$4_P$4") (pintype "bidirectional"))
      (node (ref "R_MOUNT") (pin "1") (pinfunction "1_1") (pintype "passive"))
    )
    (net (code "32") (name "Net-(U1-VOUT)") (class "Default")
      (node (ref "R1") (pin "2") (pinfunction "2_2") (pintype "passive"))
      (node (ref "U1") (pin "1") (pinfunction "VOUT_1") (pintype "output"))
    )
    (net (code "33") (name "Net-(U3-GPIO_0)") (class "Default")
      (node (ref "R3") (pin "1") (pinfunction "1_1") (pintype "passive"))
      (node (ref "U3") (pin "14") (pinfunction "GPIO_0_14") (pintype "bidirectional"))
    )
    (net (code "34") (name "Net-(U6-GPS_ANT)") (class "Default")
      (node (ref "J9") (pin "1") (pinfunction "1_1") (pintype "passive"))
      (node (ref "L2") (pin "2") (pinfunction "2_2") (pintype "passive"))
      (node (ref "U6") (pin "32") (pinfunction "GPS_ANT_32") (pintype "bidirectional"))
    )
    (net (code "35") (name "Net-(U6-GPS_BOOTSEL)") (class "Default")
      (node (ref "R4") (pin "2") (pinfunction "2_2") (pintype "passive"))
      (node (ref "R5") (pin "2") (pinfunction "2_2") (pintype "passive"))
      (node (ref "U6") (pin "9") (pinfunction "GPS_BOOTSEL_9") (pintype "bidirectional"))
    )
    (net (code "36") (name "Net-(U6-GPS_LED)") (class "Default")
      (node (ref "D1") (pin "A") (pinfunction "A_A") (pintype "passive"))
      (node (ref "U6") (pin "7") (pinfunction "GPS_LED_7") (pintype "bidirectional"))
    )
    (net (code "37") (name "PI_STATUS") (class "Default")
      (node (ref "U$1") (pin "32-OUT1B") (pinfunction "32-OUT1B_32-OUT1B") (pintype "bidirectional"))
      (node (ref "X1") (pin "8") (pinfunction "P$8_8") (pintype "bidirectional"))
    )
    (net (code "38") (name "RADIO_RESET") (class "Default")
      (node (ref "R3") (pin "2") (pinfunction "2_2") (pintype "passive"))
      (node (ref "U$1") (pin "7-RX2/OUT1A") (pinfunction "7-RX2/OUT1A_7-RX2/OUT1A") (pintype "bidirectional"))
      (node (ref "U4") (pin "6") (pinfunction "RESET_6") (pintype "bidirectional"))
    )
    (net (code "39") (name "RF_GND") (class "Default")
      (node (ref "R6") (pin "1") (pinfunction "1_1") (pintype "passive"))
      (node (ref "U6") (pin "21") (pinfunction "GND_RF_21") (pintype "bidirectional"))
      (node (ref "U6") (pin "22") (pinfunction "P$22_22") (pintype "bidirectional"))
      (node (ref "U6") (pin "24") (pinfunction "P$24_24") (pintype "bidirectional"))
      (node (ref "U6") (pin "25") (pinfunction "P$25_25") (pintype "bidirectional"))
      (node (ref "U6") (pin "27") (pinfunction "P$27_27") (pintype "bidirectional"))
      (node (ref "U6") (pin "28") (pinfunction "P$28_28") (pintype "bidirectional"))
      (node (ref "U6") (pin "29") (pinfunction "P$29_29") (pintype "bidirectional"))
      (node (ref "U6") (pin "31") (pinfunction "P$31_31") (pintype "bidirectional"))
      (node (ref "U6") (pin "33") (pinfunction "P$33_33") (pintype "bidirectional"))
    )
    (net (code "40") (name "RPI_5V_PWR_IN") (class "Default")
      (node (ref "C2") (pin "1") (pinfunction "1_1") (pintype "passive"))
      (node (ref "U2") (pin "1") (pinfunction "1_VOUT_1") (pintype "power_in"))
      (node (ref "U2") (pin "8") (pinfunction "2_VOUT_8") (pintype "power_in"))
      (node (ref "X1") (pin "2") (pinfunction "P$2_2") (pintype "bidirectional"))
    )
    (net (code "41") (name "RPI_ENABLE") (class "Default")
      (node (ref "U$1") (pin "36-PWM") (pinfunction "36-PWM_36-PWM") (pintype "bidirectional"))
      (node (ref "U2") (pin "4") (pinfunction "EN_4") (pintype "input"))
    )
    (net (code "42") (name "SCL1_I2C") (class "Default")
      (node (ref "J6") (pin "1") (pinfunction "1_1") (pintype "passive"))
      (node (ref "U$1") (pin "16-A2/RX4/SCL1") (pinfunction "16-A2/RX4/SCL1_16-A2/RX4/SCL1") (pintype "bidirectional"))
      (node (ref "X1") (pin "5") (pinfunction "P$5_5") (pintype "bidirectional"))
    )
    (net (code "43") (name "SDA1_I2C") (class "Default")
      (node (ref "J6") (pin "2") (pinfunction "2_2") (pintype "passive"))
      (node (ref "U$1") (pin "17-A3/TX4/SDA1") (pinfunction "17-A3/TX4/SDA1_17-A3/TX4/SDA1") (pintype "bidirectional"))
      (node (ref "X1") (pin "3") (pinfunction "P$3_3") (pintype "bidirectional"))
    )
    (net (code "44") (name "SPI0_CE0_N") (class "Default")
      (node (ref "J8") (pin "2") (pinfunction "2_2") (pintype "passive"))
      (node (ref "X1") (pin "24") (pinfunction "P$24_24") (pintype "bidirectional"))
    )
    (net (code "45") (name "SPI0_CE1_N") (class "Default")
      (node (ref "J8") (pin "1") (pinfunction "1_1") (pintype "passive"))
      (node (ref "X1") (pin "26") (pinfunction "P$26_26") (pintype "bidirectional"))
    )
    (net (code "46") (name "SPI0_MISO") (class "Default")
      (node (ref "J8") (pin "5") (pinfunction "5_5") (pintype "passive"))
      (node (ref "U$1") (pin "12-MISO/MQSL") (pinfunction "12-MISO/MQSL_12-MISO/MQSL") (pintype "bidirectional"))
      (node (ref "X1") (pin "21") (pinfunction "P$21_21") (pintype "bidirectional"))
    )
    (net (code "47") (name "SPI0_MOSI") (class "Default")
      (node (ref "J8") (pin "6") (pinfunction "6_6") (pintype "passive"))
      (node (ref "U$1") (pin "11-MOSI/CTX1") (pinfunction "11-MOSI/CTX1_11-MOSI/CTX1") (pintype "bidirectional"))
      (node (ref "X1") (pin "19") (pinfunction "P$19_19") (pintype "bidirectional"))
    )
    (net (code "48") (name "SPI0_SCLK") (class "Default")
      (node (ref "J8") (pin "4") (pinfunction "4_4") (pintype "passive"))
      (node (ref "U$1") (pin "13-SCK/LED") (pinfunction "13-SCK/LED_13-SCK/LED") (pintype "bidirectional"))
      (node (ref "X1") (pin "23") (pinfunction "P$23_23") (pintype "bidirectional"))
    )
    (net (code "49") (name "SPI1_CS1") (class "Default")
      (node (ref "U$1") (pin "38-A14/CS/IN1") (pinfunction "38-A14/CS/IN1_38-A14/CS/IN1") (pintype "bidirectional"))
      (node (ref "U3") (pin "5") (pinfunction "NSEL_5") (pintype "bidirectional"))
      (node (ref "U4") (pin "5") (pinfunction "NSS_5") (pintype "bidirectional"))
    )
    (net (code "50") (name "SPI1_D0") (class "Default")
      (node (ref "H1") (pin "2.2") (pinfunction "2.2_2.2") (pintype "bidirectional"))
      (node (ref "U$1") (pin "39-A15/CS/OUT1A") (pinfunction "39-A15/CS/OUT1A_39-A15/CS/OUT1A") (pintype "bidirectional"))
      (node (ref "U3") (pin "2") (pinfunction "SDO_2") (pintype "bidirectional"))
      (node (ref "U4") (pin "2") (pinfunction "MISO_2") (pintype "bidirectional"))
    )
    (net (code "51") (name "SPI1_D1") (class "Default")
      (node (ref "H1") (pin "2.3") (pinfunction "2.3_2.3") (pintype "bidirectional"))
      (node (ref "U$1") (pin "26-A12/MOSI1") (pinfunction "26-A12/MOSI1_26-A12/MOSI1") (pintype "bidirectional"))
      (node (ref "U3") (pin "3") (pinfunction "SDI_3") (pintype "bidirectional"))
      (node (ref "U4") (pin "3") (pinfunction "MOSI_3") (pintype "bidirectional"))
    )
    (net (code "52") (name "SPI1_SCLK") (class "Default")
      (node (ref "H1") (pin "2.1") (pinfunction "2.1_2.1") (pintype "bidirectional"))
      (node (ref "U$1") (pin "27-A13/SCK1") (pinfunction "27-A13/SCK1_27-A13/SCK1") (pintype "bidirectional"))
      (node (ref "U3") (pin "4") (pinfunction "SCK_4") (pintype "bidirectional"))
      (node (ref "U4") (pin "4") (pinfunction "SCK_4") (pintype "bidirectional"))
    )
    (net (code "53") (name "T_CS") (class "Default")
      (node (ref "J4") (pin "1") (pinfunction "1_1") (pintype "passive"))
      (node (ref "U$1") (pin "10-CS\\MQSR") (pinfunction "10-CS/MQSR_10-CS\\MQSR") (pintype "bidirectional"))
    )
    (net (code "54") (name "T_CS1") (class "Default")
      (node (ref "H1") (pin "2.4") (pinfunction "2.4_2.4") (pintype "bidirectional"))
      (node (ref "U$1") (pin "9-OUT1C") (pinfunction "9-OUT1C_9-OUT1C") (pintype "bidirectional"))
    )
    (net (code "55") (name "T_GPIO2") (class "Default")
      (node (ref "J3") (pin "5") (pinfunction "5_5") (pintype "passive"))
      (node (ref "U$1") (pin "2-OUT2") (pinfunction "2-OUT2_2-OUT2") (pintype "bidirectional"))
    )
    (net (code "56") (name "T_GPIO3") (class "Default")
      (node (ref "J3") (pin "4") (pinfunction "4_4") (pintype "passive"))
      (node (ref "U$1") (pin "3-LRCLK2") (pinfunction "3-LRCLK2_3-LRCLK2") (pintype "bidirectional"))
    )
    (net (code "57") (name "T_GPIO4") (class "Default")
      (node (ref "J3") (pin "3") (pinfunction "3_3") (pintype "passive"))
      (node (ref "U$1") (pin "4-BCLK2") (pinfunction "4-BCLK2_4-BCLK2") (pintype "bidirectional"))
    )
    (net (code "58") (name "T_GPIO5") (class "Default")
      (node (ref "J3") (pin "2") (pinfunction "2_2") (pintype "passive"))
      (node (ref "U$1") (pin "5-IN2") (pinfunction "5-IN2_5-IN2") (pintype "bidirectional"))
    )
    (net (code "59") (name "T_GPIO6") (class "Default")
      (node (ref "J3") (pin "1") (pinfunction "1_1") (pintype "passive"))
      (node (ref "U$1") (pin "6-OUT1D") (pinfunction "6-OUT1D_6-OUT1D") (pintype "bidirectional"))
    )
    (net (code "60") (name "T_PROGRAM") (class "Default")
      (node (ref "J11") (pin "2") (pinfunction "2_2") (pintype "passive"))
      (node (ref "U$1") (pin "PROGRAM") (pinfunction "PROGRAM_PROGRAM") (pintype "bidirectional"))
    )
    (net (code "61") (name "T_VBAT") (class "Default")
      (node (ref "J11") (pin "1") (pinfunction "1_1") (pintype "passive"))
      (node (ref "U$1") (pin "VBAT") (pinfunction "VBAT_VBAT") (pintype "bidirectional"))
    )
    (net (code "62") (name "T_VUSB") (class "Default")
      (node (ref "J12") (pin "1") (pinfunction "1_1") (pintype "passive"))
      (node (ref "U$1") (pin "VUSB") (pinfunction "VUSB_VUSB") (pintype "bidirectional"))
    )
    (net (code "63") (name "UART2_RXD") (class "Default")
      (node (ref "J2") (pin "1") (pinfunction "1_1") (pintype "passive"))
      (node (ref "U$1") (pin "34-RX8") (pinfunction "34-RX8_34-RX8") (pintype "bidirectional"))
    )
    (net (code "64") (name "UART2_TXD") (class "Default")
      (node (ref "J2") (pin "3") (pinfunction "3_3") (pintype "passive"))
      (node (ref "U$1") (pin "35-TX8") (pinfunction "35/TX8_35-TX8") (pintype "bidirectional"))
    )
    (net (code "65") (name "UART4_RXD") (class "Default")
      (node (ref "H1") (pin "1.2") (pinfunction "1.2_1.2") (pintype "bidirectional"))
      (node (ref "U$1") (pin "0-RX1/CS1/CRX2") (pinfunction "0-RX1/CS1/CRX2_0-RX1/CS1/CRX2") (pintype "bidirectional"))
    )
    (net (code "66") (name "UART4_TXD") (class "Default")
      (node (ref "H1") (pin "1.1") (pinfunction "1.1_1.1") (pintype "bidirectional"))
      (node (ref "U$1") (pin "1-TX1/MISO1/CTX2") (pinfunction "1-TX1/MISO1/CTX2_1-TX1/MISO1/CTX2") (pintype "bidirectional"))
    )
    (net (code "67") (name "UART5_RXD") (class "Default")
      (node (ref "J14") (pin "3") (pinfunction "3_3") (pintype "passive"))
      (node (ref "U$1") (pin "29-TX7") (pinfunction "29-TX7_29-TX7") (pintype "bidirectional"))
      (node (ref "U6") (pin "42") (pinfunction "GPS_RXDO_42") (pintype "input"))
    )
    (net (code "68") (name "UART5_TXD") (class "Default")
      (node (ref "J14") (pin "4") (pinfunction "4_4") (pintype "passive"))
      (node (ref "U$1") (pin "28-RX7") (pinfunction "28-RX7_28-RX7") (pintype "bidirectional"))
      (node (ref "U6") (pin "44") (pinfunction "GPS_TXD0_44") (pintype "output"))
    )
    (net (code "69") (name "USB_DEV_D+") (class "Default")
      (node (ref "J12") (pin "4") (pinfunction "4_4") (pintype "passive"))
      (node (ref "U$1") (pin "D+") (pinfunction "D+_D+") (pintype "bidirectional"))
    )
    (net (code "70") (name "USB_DEV_D-") (class "Default")
      (node (ref "J12") (pin "3") (pinfunction "3_3") (pintype "passive"))
      (node (ref "U$1") (pin "D-") (pinfunction "D-_D-") (pintype "bidirectional"))
    )
    (net (code "71") (name "USB_HOST_D+") (class "Default")
      (node (ref "J13") (pin "1") (pinfunction "1_1") (pintype "passive"))
      (node (ref "U$1") (pin "DP") (pinfunction "DP_DP") (pintype "bidirectional"))
    )
    (net (code "72") (name "USB_HOST_D-") (class "Default")
      (node (ref "J13") (pin "2") (pinfunction "2_2") (pintype "passive"))
      (node (ref "U$1") (pin "DM") (pinfunction "DM_DM") (pintype "bidirectional"))
    )
    (net (code "73") (name "unconnected-(H1-Pad1.9)") (class "Default")
      (node (ref "H1") (pin "1.9") (pinfunction "1.9_1.9") (pintype "bidirectional"))
    )
    (net (code "74") (name "unconnected-(H1-Pad1.10)") (class "Default")
      (node (ref "H1") (pin "1.10") (pinfunction "1.10_1.10") (pintype "bidirectional"))
    )
    (net (code "75") (name "unconnected-(H1-Pad1.11)") (class "Default")
      (node (ref "H1") (pin "1.11") (pinfunction "1.11_1.11") (pintype "bidirectional"))
    )
    (net (code "76") (name "unconnected-(H1-Pad1.12)") (class "Default")
      (node (ref "H1") (pin "1.12") (pinfunction "1.12_1.12") (pintype "bidirectional"))
    )
    (net (code "77") (name "unconnected-(H1-Pad1.13)") (class "Default")
      (node (ref "H1") (pin "1.13") (pinfunction "1.13_1.13") (pintype "bidirectional"))
    )
    (net (code "78") (name "unconnected-(H1-Pad1.14)") (class "Default")
      (node (ref "H1") (pin "1.14") (pinfunction "1.14_1.14") (pintype "bidirectional"))
    )
    (net (code "79") (name "unconnected-(H1-Pad1.15)") (class "Default")
      (node (ref "H1") (pin "1.15") (pinfunction "1.15_1.15") (pintype "bidirectional"))
    )
    (net (code "80") (name "unconnected-(H1-Pad1.16)") (class "Default")
      (node (ref "H1") (pin "1.16") (pinfunction "1.16_1.16") (pintype "bidirectional"))
    )
    (net (code "81") (name "unconnected-(H1-Pad1.17)") (class "Default")
      (node (ref "H1") (pin "1.17") (pinfunction "1.17_1.17") (pintype "bidirectional"))
    )
    (net (code "82") (name "unconnected-(H1-Pad1.18)") (class "Default")
      (node (ref "H1") (pin "1.18") (pinfunction "1.18_1.18") (pintype "bidirectional"))
    )
    (net (code "83") (name "unconnected-(H1-Pad1.19)") (class "Default")
      (node (ref "H1") (pin "1.19") (pinfunction "1.19_1.19") (pintype "bidirectional"))
    )
    (net (code "84") (name "unconnected-(H1-Pad1.20)") (class "Default")
      (node (ref "H1") (pin "1.20") (pinfunction "1.20_1.20") (pintype "bidirectional"))
    )
    (net (code "85") (name "unconnected-(H1-Pad1.21)") (class "Default")
      (node (ref "H1") (pin "1.21") (pinfunction "1.21_1.21") (pintype "bidirectional"))
    )
    (net (code "86") (name "unconnected-(H1-Pad1.22)") (class "Default")
      (node (ref "H1") (pin "1.22") (pinfunction "1.22_1.22") (pintype "bidirectional"))
    )
    (net (code "87") (name "unconnected-(H1-Pad1.23)") (class "Default")
      (node (ref "H1") (pin "1.23") (pinfunction "1.23_1.23") (pintype "bidirectional"))
    )
    (net (code "88") (name "unconnected-(H1-Pad1.24)") (class "Default")
      (node (ref "H1") (pin "1.24") (pinfunction "1.24_1.24") (pintype "bidirectional"))
    )
    (net (code "89") (name "unconnected-(H1-Pad1.25)") (class "Default")
      (node (ref "H1") (pin "1.25") (pinfunction "1.25_1.25") (pintype "bidirectional"))
    )
    (net (code "90") (name "unconnected-(H1-Pad1.26)") (class "Default")
      (node (ref "H1") (pin "1.26") (pinfunction "1.26_1.26") (pintype "bidirectional"))
    )
    (net (code "91") (name "unconnected-(H1-Pad1.27)") (class "Default")
      (node (ref "H1") (pin "1.27") (pinfunction "1.27_1.27") (pintype "bidirectional"))
    )
    (net (code "92") (name "unconnected-(H1-Pad1.28)") (class "Default")
      (node (ref "H1") (pin "1.28") (pinfunction "1.28_1.28") (pintype "bidirectional"))
    )
    (net (code "93") (name "unconnected-(H1-Pad1.29)") (class "Default")
      (node (ref "H1") (pin "1.29") (pinfunction "1.29_1.29") (pintype "bidirectional"))
    )
    (net (code "94") (name "unconnected-(H1-Pad1.30)") (class "Default")
      (node (ref "H1") (pin "1.30") (pinfunction "1.30_1.30") (pintype "bidirectional"))
    )
    (net (code "95") (name "unconnected-(H1-Pad1.31)") (class "Default")
      (node (ref "H1") (pin "1.31") (pinfunction "1.31_1.31") (pintype "bidirectional"))
    )
    (net (code "96") (name "unconnected-(H1-Pad1.32)") (class "Default")
      (node (ref "H1") (pin "1.32") (pinfunction "1.32_1.32") (pintype "bidirectional"))
    )
    (net (code "97") (name "unconnected-(H1-Pad1.33)") (class "Default")
      (node (ref "H1") (pin "1.33") (pinfunction "1.33_1.33") (pintype "bidirectional"))
    )
    (net (code "98") (name "unconnected-(H1-Pad1.34)") (class "Default")
      (node (ref "H1") (pin "1.34") (pinfunction "1.34_1.34") (pintype "bidirectional"))
    )
    (net (code "99") (name "unconnected-(H1-Pad1.35)") (class "Default")
      (node (ref "H1") (pin "1.35") (pinfunction "1.35_1.35") (pintype "bidirectional"))
    )
    (net (code "100") (name "unconnected-(H1-Pad1.36)") (class "Default")
      (node (ref "H1") (pin "1.36") (pinfunction "1.36_1.36") (pintype "bidirectional"))
    )
    (net (code "101") (name "unconnected-(H1-Pad1.37)") (class "Default")
      (node (ref "H1") (pin "1.37") (pinfunction "1.37_1.37") (pintype "bidirectional"))
    )
    (net (code "102") (name "unconnected-(H1-Pad1.38)") (class "Default")
      (node (ref "H1") (pin "1.38") (pinfunction "1.38_1.38") (pintype "bidirectional"))
    )
    (net (code "103") (name "unconnected-(H1-Pad1.39)") (class "Default")
      (node (ref "H1") (pin "1.39") (pinfunction "1.39_1.39") (pintype "bidirectional"))
    )
    (net (code "104") (name "unconnected-(H1-Pad1.40)") (class "Default")
      (node (ref "H1") (pin "1.40") (pinfunction "1.40_1.40") (pintype "bidirectional"))
    )
    (net (code "105") (name "unconnected-(H1-Pad1.42)") (class "Default")
      (node (ref "H1") (pin "1.42") (pinfunction "1.42_1.42") (pintype "bidirectional"))
    )
    (net (code "106") (name "unconnected-(H1-Pad1.44)") (class "Default")
      (node (ref "H1") (pin "1.44") (pinfunction "1.44_1.44") (pintype "bidirectional"))
    )
    (net (code "107") (name "unconnected-(H1-Pad1.45)") (class "Default")
      (node (ref "H1") (pin "1.45") (pinfunction "1.45_1.45") (pintype "bidirectional"))
    )
    (net (code "108") (name "unconnected-(H1-Pad1.46)") (class "Default")
      (node (ref "H1") (pin "1.46") (pinfunction "1.46_1.46") (pintype "bidirectional"))
    )
    (net (code "109") (name "unconnected-(H1-Pad1.47)") (class "Default")
      (node (ref "H1") (pin "1.47") (pinfunction "1.47_1.47") (pintype "bidirectional"))
    )
    (net (code "110") (name "unconnected-(H1-Pad1.48)") (class "Default")
      (node (ref "H1") (pin "1.48") (pinfunction "1.48_1.48") (pintype "bidirectional"))
    )
    (net (code "111") (name "unconnected-(H1-Pad1.49)") (class "Default")
      (node (ref "H1") (pin "1.49") (pinfunction "1.49_1.49") (pintype "bidirectional"))
    )
    (net (code "112") (name "unconnected-(H1-Pad1.50)") (class "Default")
      (node (ref "H1") (pin "1.50") (pinfunction "1.50_1.50") (pintype "bidirectional"))
    )
    (net (code "113") (name "unconnected-(H1-Pad1.51)") (class "Default")
      (node (ref "H1") (pin "1.51") (pinfunction "1.51_1.51") (pintype "bidirectional"))
    )
    (net (code "114") (name "unconnected-(H1-Pad1.52)") (class "Default")
      (node (ref "H1") (pin "1.52") (pinfunction "1.52_1.52") (pintype "bidirectional"))
    )
    (net (code "115") (name "unconnected-(H1-Pad2.5)") (class "Default")
      (node (ref "H1") (pin "2.5") (pinfunction "2.5_2.5") (pintype "bidirectional"))
    )
    (net (code "116") (name "unconnected-(H1-Pad2.6)") (class "Default")
      (node (ref "H1") (pin "2.6") (pinfunction "2.6_2.6") (pintype "bidirectional"))
    )
    (net (code "117") (name "unconnected-(H1-Pad2.8)") (class "Default")
      (node (ref "H1") (pin "2.8") (pinfunction "2.8_2.8") (pintype "bidirectional"))
    )
    (net (code "118") (name "unconnected-(H1-Pad2.9)") (class "Default")
      (node (ref "H1") (pin "2.9") (pinfunction "2.9_2.9") (pintype "bidirectional"))
    )
    (net (code "119") (name "unconnected-(H1-Pad2.10)") (class "Default")
      (node (ref "H1") (pin "2.10") (pinfunction "2.10_2.10") (pintype "bidirectional"))
    )
    (net (code "120") (name "unconnected-(H1-Pad2.11)") (class "Default")
      (node (ref "H1") (pin "2.11") (pinfunction "2.11_2.11") (pintype "bidirectional"))
    )
    (net (code "121") (name "unconnected-(H1-Pad2.12)") (class "Default")
      (node (ref "H1") (pin "2.12") (pinfunction "2.12_2.12") (pintype "bidirectional"))
    )
    (net (code "122") (name "unconnected-(H1-Pad2.13)") (class "Default")
      (node (ref "H1") (pin "2.13") (pinfunction "2.13_2.13") (pintype "bidirectional"))
    )
    (net (code "123") (name "unconnected-(H1-Pad2.15)") (class "Default")
      (node (ref "H1") (pin "2.15") (pinfunction "2.15_2.15") (pintype "bidirectional"))
    )
    (net (code "124") (name "unconnected-(H1-Pad2.16)") (class "Default")
      (node (ref "H1") (pin "2.16") (pinfunction "2.16_2.16") (pintype "bidirectional"))
    )
    (net (code "125") (name "unconnected-(H1-Pad2.18)") (class "Default")
      (node (ref "H1") (pin "2.18") (pinfunction "2.18_2.18") (pintype "bidirectional"))
    )
    (net (code "126") (name "unconnected-(H1-Pad2.19)") (class "Default")
      (node (ref "H1") (pin "2.19") (pinfunction "2.19_2.19") (pintype "bidirectional"))
    )
    (net (code "127") (name "unconnected-(H1-Pad2.20)") (class "Default")
      (node (ref "H1") (pin "2.20") (pinfunction "2.20_2.20") (pintype "bidirectional"))
    )
    (net (code "128") (name "unconnected-(H1-Pad2.23)") (class "Default")
      (node (ref "H1") (pin "2.23") (pinfunction "2.23_2.23") (pintype "bidirectional"))
    )
    (net (code "129") (name "unconnected-(H1-Pad2.24)") (class "Default")
      (node (ref "H1") (pin "2.24") (pinfunction "2.24_2.24") (pintype "bidirectional"))
    )
    (net (code "130") (name "unconnected-(H1-Pad2.31)") (class "Default")
      (node (ref "H1") (pin "2.31") (pinfunction "2.31_2.31") (pintype "bidirectional"))
    )
    (net (code "131") (name "unconnected-(H1-Pad2.33)") (class "Default")
      (node (ref "H1") (pin "2.33") (pinfunction "2.33_2.33") (pintype "bidirectional"))
    )
    (net (code "132") (name "unconnected-(H1-Pad2.34)") (class "Default")
      (node (ref "H1") (pin "2.34") (pinfunction "2.34_2.34") (pintype "bidirectional"))
    )
    (net (code "133") (name "unconnected-(H1-Pad2.35)") (class "Default")
      (node (ref "H1") (pin "2.35") (pinfunction "2.35_2.35") (pintype "bidirectional"))
    )
    (net (code "134") (name "unconnected-(H1-Pad2.36)") (class "Default")
      (node (ref "H1") (pin "2.36") (pinfunction "2.36_2.36") (pintype "bidirectional"))
    )
    (net (code "135") (name "unconnected-(H1-Pad2.37)") (class "Default")
      (node (ref "H1") (pin "2.37") (pinfunction "2.37_2.37") (pintype "bidirectional"))
    )
    (net (code "136") (name "unconnected-(H1-Pad2.38)") (class "Default")
      (node (ref "H1") (pin "2.38") (pinfunction "2.38_2.38") (pintype "bidirectional"))
    )
    (net (code "137") (name "unconnected-(H1-Pad2.39)") (class "Default")
      (node (ref "H1") (pin "2.39") (pinfunction "2.39_2.39") (pintype "bidirectional"))
    )
    (net (code "138") (name "unconnected-(H1-Pad2.40)") (class "Default")
      (node (ref "H1") (pin "2.40") (pinfunction "2.40_2.40") (pintype "bidirectional"))
    )
    (net (code "139") (name "unconnected-(H1-Pad2.41)") (class "Default")
      (node (ref "H1") (pin "2.41") (pinfunction "2.41_2.41") (pintype "bidirectional"))
    )
    (net (code "140") (name "unconnected-(H1-Pad2.42)") (class "Default")
      (node (ref "H1") (pin "2.42") (pinfunction "2.42_2.42") (pintype "bidirectional"))
    )
    (net (code "141") (name "unconnected-(H1-Pad2.43)") (class "Default")
      (node (ref "H1") (pin "2.43") (pinfunction "2.43_2.43") (pintype "bidirectional"))
    )
    (net (code "142") (name "unconnected-(H1-Pad2.44)") (class "Default")
      (node (ref "H1") (pin "2.44") (pinfunction "2.44_2.44") (pintype "bidirectional"))
    )
    (net (code "143") (name "unconnected-(H1-Pad2.45)") (class "Default")
      (node (ref "H1") (pin "2.45") (pinfunction "2.45_2.45") (pintype "bidirectional"))
    )
    (net (code "144") (name "unconnected-(H1-Pad2.46)") (class "Default")
      (node (ref "H1") (pin "2.46") (pinfunction "2.46_2.46") (pintype "bidirectional"))
    )
    (net (code "145") (name "unconnected-(H1-Pad2.49)") (class "Default")
      (node (ref "H1") (pin "2.49") (pinfunction "2.49_2.49") (pintype "bidirectional"))
    )
    (net (code "146") (name "unconnected-(H1-Pad2.50)") (class "Default")
      (node (ref "H1") (pin "2.50") (pinfunction "2.50_2.50") (pintype "bidirectional"))
    )
    (net (code "147") (name "unconnected-(H1-Pad2.51)") (class "Default")
      (node (ref "H1") (pin "2.51") (pinfunction "2.51_2.51") (pintype "bidirectional"))
    )
    (net (code "148") (name "unconnected-(H1-Pad2.52)") (class "Default")
      (node (ref "H1") (pin "2.52") (pinfunction "2.52_2.52") (pintype "bidirectional"))
    )
    (net (code "149") (name "unconnected-(H1-PadP$1)") (class "Default")
      (node (ref "H1") (pin "P$1") (pinfunction "P$1_P$1") (pintype "bidirectional"))
    )
    (net (code "150") (name "unconnected-(H1-PadP$2)") (class "Default")
      (node (ref "H1") (pin "P$2") (pinfunction "P$2_P$2") (pintype "bidirectional"))
    )
    (net (code "151") (name "unconnected-(H1-PadP$3)") (class "Default")
      (node (ref "H1") (pin "P$3") (pinfunction "P$3_P$3") (pintype "bidirectional"))
    )
    (net (code "152") (name "unconnected-(U$1-Pad30-CRX3)") (class "Default")
      (node (ref "U$1") (pin "30-CRX3") (pinfunction "30-CRX3_30-CRX3") (pintype "bidirectional"))
    )
    (net (code "153") (name "unconnected-(U$1-Pad31-CTX3)") (class "Default")
      (node (ref "U$1") (pin "31-CTX3") (pinfunction "31-CTX3_31-CTX3") (pintype "bidirectional"))
    )
    (net (code "154") (name "unconnected-(U$1-Pad37-PWM)") (class "Default")
      (node (ref "U$1") (pin "37-PWM") (pinfunction "37-PWM_37-PWM") (pintype "bidirectional"))
    )
    (net (code "155") (name "unconnected-(U$1-Pad40-A16{slash}CS1)") (class "Default")
      (node (ref "U$1") (pin "40-A16/CS1") (pinfunction "40-A16/CS1_40-A16/CS1") (pintype "bidirectional"))
    )
    (net (code "156") (name "unconnected-(U$1-PadON{slash}OFF)") (class "Default")
      (node (ref "U$1") (pin "ON/OFF") (pinfunction "ON/OFF_ON/OFF") (pintype "bidirectional"))
    )
    (net (code "157") (name "unconnected-(U1-NC-Pad7)") (class "Default")
      (node (ref "U1") (pin "7") (pinfunction "NC_7") (pintype "no_connect"))
    )
    (net (code "158") (name "unconnected-(U1-NC_2-Pad2)") (class "Default")
      (node (ref "U1") (pin "2") (pinfunction "NC_2_2") (pintype "no_connect"))
    )
    (net (code "159") (name "unconnected-(U1-NC_3-Pad3)") (class "Default")
      (node (ref "U1") (pin "3") (pinfunction "NC_3_3") (pintype "no_connect"))
    )
    (net (code "160") (name "unconnected-(U1-NC_4-Pad6)") (class "Default")
      (node (ref "U1") (pin "6") (pinfunction "NC_4_6") (pintype "no_connect"))
    )
    (net (code "161") (name "unconnected-(U3-GPIO_2-Pad16)") (class "Default")
      (node (ref "U3") (pin "16") (pinfunction "GPIO_2_16") (pintype "bidirectional"))
    )
    (net (code "162") (name "unconnected-(U3-NIRQ-Pad6)") (class "Default")
      (node (ref "U3") (pin "6") (pinfunction "NIRQ_6") (pintype "bidirectional"))
    )
    (net (code "163") (name "unconnected-(U3-RXON-Pad12)") (class "Default")
      (node (ref "U3") (pin "12") (pinfunction "RXON_12") (pintype "bidirectional"))
    )
    (net (code "164") (name "unconnected-(U3-SDN-Pad7)") (class "Default")
      (node (ref "U3") (pin "7") (pinfunction "SDN_7") (pintype "bidirectional"))
    )
    (net (code "165") (name "unconnected-(U3-TXON-Pad11)") (class "Default")
      (node (ref "U3") (pin "11") (pinfunction "TXON_11") (pintype "bidirectional"))
    )
    (net (code "166") (name "unconnected-(U4-DIO0-Pad14)") (class "Default")
      (node (ref "U4") (pin "14") (pinfunction "DIO0_14") (pintype "bidirectional"))
    )
    (net (code "167") (name "unconnected-(U4-DIO2-Pad16)") (class "Default")
      (node (ref "U4") (pin "16") (pinfunction "DIO2_16") (pintype "bidirectional"))
    )
    (net (code "168") (name "unconnected-(U4-DIO3-Pad11)") (class "Default")
      (node (ref "U4") (pin "11") (pinfunction "DIO3_11") (pintype "bidirectional"))
    )
    (net (code "169") (name "unconnected-(U4-DIO4-Pad12)") (class "Default")
      (node (ref "U4") (pin "12") (pinfunction "DIO4_12") (pintype "bidirectional"))
    )
    (net (code "170") (name "unconnected-(U4-DIO5-Pad7)") (class "Default")
      (node (ref "U4") (pin "7") (pinfunction "DIO5_7") (pintype "bidirectional"))
    )
    (net (code "171") (name "unconnected-(U5-Pad1)") (class "Default")
      (node (ref "U5") (pin "1") (pinfunction "1_1") (pintype "passive"))
    )
    (net (code "172") (name "unconnected-(U6-P$3-Pad3)") (class "Default")
      (node (ref "U6") (pin "3") (pinfunction "P$3_3") (pintype "bidirectional"))
    )
    (net (code "173") (name "unconnected-(U6-P$4-Pad4)") (class "Default")
      (node (ref "U6") (pin "4") (pinfunction "P$4_4") (pintype "bidirectional"))
    )
    (net (code "174") (name "unconnected-(U6-P$5-Pad5)") (class "Default")
      (node (ref "U6") (pin "5") (pinfunction "P$5_5") (pintype "bidirectional"))
    )
    (net (code "175") (name "unconnected-(U6-P$6-Pad6)") (class "Default")
      (node (ref "U6") (pin "6") (pinfunction "P$6_6") (pintype "bidirectional"))
    )
    (net (code "176") (name "unconnected-(U6-P$8-Pad8)") (class "Default")
      (node (ref "U6") (pin "8") (pinfunction "P$8_8") (pintype "bidirectional"))
    )
    (net (code "177") (name "unconnected-(U6-P$12-Pad12)") (class "Default")
      (node (ref "U6") (pin "12") (pinfunction "P$12_12") (pintype "bidirectional"))
    )
    (net (code "178") (name "unconnected-(U6-P$13-Pad13)") (class "Default")
      (node (ref "U6") (pin "13") (pinfunction "P$13_13") (pintype "bidirectional"))
    )
    (net (code "179") (name "unconnected-(U6-P$14-Pad14)") (class "Default")
      (node (ref "U6") (pin "14") (pinfunction "P$14_14") (pintype "bidirectional"))
    )
    (net (code "180") (name "unconnected-(U6-P$16-Pad16)") (class "Default")
      (node (ref "U6") (pin "16") (pinfunction "P$16_16") (pintype "bidirectional"))
    )
    (net (code "181") (name "unconnected-(U6-P$17-Pad17)") (class "Default")
      (node (ref "U6") (pin "17") (pinfunction "P$17_17") (pintype "bidirectional"))
    )
    (net (code "182") (name "unconnected-(U6-P$20-Pad20)") (class "Default")
      (node (ref "U6") (pin "20") (pinfunction "P$20_20") (pintype "bidirectional"))
    )
    (net (code "183") (name "unconnected-(U6-P$23-Pad23)") (class "Default")
      (node (ref "U6") (pin "23") (pinfunction "P$23_23") (pintype "bidirectional"))
    )
    (net (code "184") (name "unconnected-(U6-P$26-Pad26)") (class "Default")
      (node (ref "U6") (pin "26") (pinfunction "P$26_26") (pintype "bidirectional"))
    )
    (net (code "185") (name "unconnected-(U6-P$30-Pad30)") (class "Default")
      (node (ref "U6") (pin "30") (pinfunction "P$30_30") (pintype "bidirectional"))
    )
    (net (code "186") (name "unconnected-(U6-P$34-Pad34)") (class "Default")
      (node (ref "U6") (pin "34") (pinfunction "P$34_34") (pintype "bidirectional"))
    )
    (net (code "187") (name "unconnected-(U6-P$35-Pad35)") (class "Default")
      (node (ref "U6") (pin "35") (pinfunction "P$35_35") (pintype "bidirectional"))
    )
    (net (code "188") (name "unconnected-(U6-P$36-Pad36)") (class "Default")
      (node (ref "U6") (pin "36") (pinfunction "P$36_36") (pintype "bidirectional"))
    )
    (net (code "189") (name "unconnected-(U6-P$37-Pad37)") (class "Default")
      (node (ref "U6") (pin "37") (pinfunction "P$37_37") (pintype "bidirectional"))
    )
    (net (code "190") (name "unconnected-(U6-P$38-Pad38)") (class "Default")
      (node (ref "U6") (pin "38") (pinfunction "P$38_38") (pintype "bidirectional"))
    )
    (net (code "191") (name "unconnected-(U6-P$39-Pad39)") (class "Default")
      (node (ref "U6") (pin "39") (pinfunction "P$39_39") (pintype "bidirectional"))
    )
    (net (code "192") (name "unconnected-(U6-P$40-Pad40)") (class "Default")
      (node (ref "U6") (pin "40") (pinfunction "P$40_40") (pintype "bidirectional"))
    )
    (net (code "193") (name "unconnected-(U6-P$41-Pad41)") (class "Default")
      (node (ref "U6") (pin "41") (pinfunction "P$41_41") (pintype "bidirectional"))
    )
    (net (code "194") (name "unconnected-(U6-P$43-Pad43)") (class "Default")
      (node (ref "U6") (pin "43") (pinfunction "P$43_43") (pintype "bidirectional"))
    )
    (net (code "195") (name "unconnected-(U6-P$45-Pad45)") (class "Default")
      (node (ref "U6") (pin "45") (pinfunction "P$45_45") (pintype "bidirectional"))
    )
    (net (code "196") (name "unconnected-(U6-P$46-Pad46)") (class "Default")
      (node (ref "U6") (pin "46") (pinfunction "P$46_46") (pintype "bidirectional"))
    )
    (net (code "197") (name "unconnected-(U6-P$47-Pad47)") (class "Default")
      (node (ref "U6") (pin "47") (pinfunction "P$47_47") (pintype "bidirectional"))
    )
    (net (code "198") (name "unconnected-(U6-P$48-Pad48)") (class "Default")
      (node (ref "U6") (pin "48") (pinfunction "P$48_48") (pintype "bidirectional"))
    )
    (net (code "199") (name "unconnected-(U6-P$49-Pad49)") (class "Default")
      (node (ref "U6") (pin "49") (pinfunction "P$49_49") (pintype "bidirectional"))
    )
    (net (code "200") (name "unconnected-(U6-P$50-Pad50)") (class "Default")
      (node (ref "U6") (pin "50") (pinfunction "P$50_50") (pintype "bidirectional"))
    )
    (net (code "201") (name "unconnected-(U6-P$51-Pad51)") (class "Default")
      (node (ref "U6") (pin "51") (pinfunction "P$51_51") (pintype "bidirectional"))
    )
    (net (code "202") (name "unconnected-(U6-P$52-Pad52)") (class "Default")
      (node (ref "U6") (pin "52") (pinfunction "P$52_52") (pintype "bidirectional"))
    )
    (net (code "203") (name "unconnected-(U6-P$53-Pad53)") (class "Default")
      (node (ref "U6") (pin "53") (pinfunction "P$53_53") (pintype "bidirectional"))
    )
    (net (code "204") (name "unconnected-(U6-P$54-Pad54)") (class "Default")
      (node (ref "U6") (pin "54") (pinfunction "P$54_54") (pintype "bidirectional"))
    )
    (net (code "205") (name "unconnected-(U6-P$55-Pad55)") (class "Default")
      (node (ref "U6") (pin "55") (pinfunction "P$55_55") (pintype "bidirectional"))
    )
    (net (code "206") (name "unconnected-(U6-P$56-Pad56)") (class "Default")
      (node (ref "U6") (pin "56") (pinfunction "P$56_56") (pintype "bidirectional"))
    )
    (net (code "207") (name "unconnected-(U6-P$57-Pad57)") (class "Default")
      (node (ref "U6") (pin "57") (pinfunction "P$57_57") (pintype "bidirectional"))
    )
    (net (code "208") (name "unconnected-(U6-P$59-Pad59)") (class "Default")
      (node (ref "U6") (pin "59") (pinfunction "P$59_59") (pintype "bidirectional"))
    )
    (net (code "209") (name "unconnected-(U6-P$60-Pad60)") (class "Default")
      (node (ref "U6") (pin "60") (pinfunction "P$60_60") (pintype "bidirectional"))
    )
    (net (code "210") (name "unconnected-(U6-P$61-Pad61)") (class "Default")
      (node (ref "U6") (pin "61") (pinfunction "P$61_61") (pintype "bidirectional"))
    )
    (net (code "211") (name "unconnected-(U6-P$62-Pad62)") (class "Default")
      (node (ref "U6") (pin "62") (pinfunction "P$62_62") (pintype "bidirectional"))
    )
    (net (code "212") (name "unconnected-(U6-P$63-Pad63)") (class "Default")
      (node (ref "U6") (pin "63") (pinfunction "P$63_63") (pintype "bidirectional"))
    )
    (net (code "213") (name "unconnected-(U6-P$65-Pad65)") (class "Default")
      (node (ref "U6") (pin "65") (pinfunction "P$65_65") (pintype "bidirectional"))
    )
    (net (code "214") (name "unconnected-(U6-P$66-Pad66)") (class "Default")
      (node (ref "U6") (pin "66") (pinfunction "P$66_66") (pintype "bidirectional"))
    )
    (net (code "215") (name "unconnected-(U6-P$67-Pad67)") (class "Default")
      (node (ref "U6") (pin "67") (pinfunction "P$67_67") (pintype "bidirectional"))
    )
    (net (code "216") (name "unconnected-(U6-P$68-Pad68)") (class "Default")
      (node (ref "U6") (pin "68") (pinfunction "P$68_68") (pintype "bidirectional"))
    )
    (net (code "217") (name "unconnected-(U6-P$69-Pad69)") (class "Default")
      (node (ref "U6") (pin "69") (pinfunction "P$69_69") (pintype "bidirectional"))
    )
    (net (code "218") (name "unconnected-(X1-P$1-Pad1)") (class "Default")
      (node (ref "X1") (pin "1") (pinfunction "P$1_1") (pintype "bidirectional"))
    )
    (net (code "219") (name "unconnected-(X1-P$4-Pad4)") (class "Default")
      (node (ref "X1") (pin "4") (pinfunction "P$4_4") (pintype "bidirectional"))
    )
    (net (code "220") (name "unconnected-(X1-P$6-Pad6)") (class "Default")
      (node (ref "X1") (pin "6") (pinfunction "P$6_6") (pintype "bidirectional"))
    )
    (net (code "221") (name "unconnected-(X1-P$7-Pad7)") (class "Default")
      (node (ref "X1") (pin "7") (pinfunction "P$7_7") (pintype "bidirectional"))
    )
    (net (code "222") (name "unconnected-(X1-P$9-Pad9)") (class "Default")
      (node (ref "X1") (pin "9") (pinfunction "P$9_9") (pintype "bidirectional"))
    )
    (net (code "223") (name "unconnected-(X1-P$10-Pad10)") (class "Default")
      (node (ref "X1") (pin "10") (pinfunction "P$10_10") (pintype "bidirectional"))
    )
    (net (code "224") (name "unconnected-(X1-P$12-Pad12)") (class "Default")
      (node (ref "X1") (pin "12") (pinfunction "P$12_12") (pintype "bidirectional"))
    )
    (net (code "225") (name "unconnected-(X1-P$14-Pad14)") (class "Default")
      (node (ref "X1") (pin "14") (pinfunction "P$14_14") (pintype "bidirectional"))
    )
    (net (code "226") (name "unconnected-(X1-P$17-Pad17)") (class "Default")
      (node (ref "X1") (pin "17") (pinfunction "P$17_17") (pintype "bidirectional"))
    )
    (net (code "227") (name "unconnected-(X1-P$20-Pad20)") (class "Default")
      (node (ref "X1") (pin "20") (pinfunction "P$20_20") (pintype "bidirectional"))
    )
    (net (code "228") (name "unconnected-(X1-P$25-Pad25)") (class "Default")
      (node (ref "X1") (pin "25") (pinfunction "P$25_25") (pintype "bidirectional"))
    )
    (net (code "229") (name "unconnected-(X1-P$27-Pad27)") (class "Default")
      (node (ref "X1") (pin "27") (pinfunction "P$27_27") (pintype "bidirectional"))
    )
    (net (code "230") (name "unconnected-(X1-P$28-Pad28)") (class "Default")
      (node (ref "X1") (pin "28") (pinfunction "P$28_28") (pintype "bidirectional"))
    )
    (net (code "231") (name "unconnected-(X1-P$29-Pad29)") (class "Default")
      (node (ref "X1") (pin "29") (pinfunction "P$29_29") (pintype "bidirectional"))
    )
    (net (code "232") (name "unconnected-(X1-P$30-Pad30)") (class "Default")
      (node (ref "X1") (pin "30") (pinfunction "P$30_30") (pintype "bidirectional"))
    )
    (net (code "233") (name "unconnected-(X1-P$31-Pad31)") (class "Default")
      (node (ref "X1") (pin "31") (pinfunction "P$31_31") (pintype "bidirectional"))
    )
    (net (code "234") (name "unconnected-(X1-P$32-Pad32)") (class "Default")
      (node (ref "X1") (pin "32") (pinfunction "P$32_32") (pintype "bidirectional"))
    )
    (net (code "235") (name "unconnected-(X1-P$33-Pad33)") (class "Default")
      (node (ref "X1") (pin "33") (pinfunction "P$33_33") (pintype "bidirectional"))
    )
    (net (code "236") (name "unconnected-(X1-P$34-Pad34)") (class "Default")
      (node (ref "X1") (pin "34") (pinfunction "P$34_34") (pintype "bidirectional"))
    )
    (net (code "237") (name "unconnected-(X1-P$35-Pad35)") (class "Default")
      (node (ref "X1") (pin "35") (pinfunction "P$35_35") (pintype "bidirectional"))
    )
    (net (code "238") (name "unconnected-(X1-P$36-Pad36)") (class "Default")
      (node (ref "X1") (pin "36") (pinfunction "P$36_36") (pintype "bidirectional"))
    )
    (net (code "239") (name "unconnected-(X1-P$37-Pad37)") (class "Default")
      (node (ref "X1") (pin "37") (pinfunction "P$37_37") (pintype "bidirectional"))
    )
    (net (code "240") (name "unconnected-(X1-P$38-Pad38)") (class "Default")
      (node (ref "X1") (pin "38") (pinfunction "P$38_38") (pintype "bidirectional"))
    )
    (net (code "241") (name "unconnected-(X1-P$40-Pad40)") (class "Default")
      (node (ref "X1") (pin "40") (pinfunction "P$40_40") (pintype "bidirectional"))
    )
    (net (code "242") (name "unconnected-(X2-Pad1)") (class "Default")
      (node (ref "X2") (pin "1") (pinfunction "1_1") (pintype "passive"))
    )
    (net (code "243") (name "unconnected-(X2AA-1-Pad33)") (class "Default")
      (node (ref "X2") (pin "33") (pinfunction "1_33") (pintype "passive"))
    )
    (net (code "244") (name "unconnected-(X2AB-1-Pad34)") (class "Default")
      (node (ref "X2") (pin "34") (pinfunction "1_34") (pintype "passive"))
    )
    (net (code "245") (name "unconnected-(X2AC-1-Pad35)") (class "Default")
      (node (ref "X2") (pin "35") (pinfunction "1_35") (pintype "passive"))
    )
    (net (code "246") (name "unconnected-(X2AD-1-Pad36)") (class "Default")
      (node (ref "X2") (pin "36") (pinfunction "1_36") (pintype "passive"))
    )
    (net (code "247") (name "unconnected-(X2AE-1-Pad37)") (class "Default")
      (node (ref "X2") (pin "37") (pinfunction "1_37") (pintype "passive"))
    )
    (net (code "248") (name "unconnected-(X2AF-1-Pad38)") (class "Default")
      (node (ref "X2") (pin "38") (pinfunction "1_38") (pintype "passive"))
    )
    (net (code "249") (name "unconnected-(X2AG-1-Pad39)") (class "Default")
      (node (ref "X2") (pin "39") (pinfunction "1_39") (pintype "passive"))
    )
    (net (code "250") (name "unconnected-(X2AH-1-Pad4)") (class "Default")
      (node (ref "X2") (pin "4") (pinfunction "1_4") (pintype "passive"))
    )
    (net (code "251") (name "unconnected-(X2AI-1-Pad40)") (class "Default")
      (node (ref "X2") (pin "40") (pinfunction "1_40") (pintype "passive"))
    )
    (net (code "252") (name "unconnected-(X2AJ-1-Pad5)") (class "Default")
      (node (ref "X2") (pin "5") (pinfunction "1_5") (pintype "passive"))
    )
    (net (code "253") (name "unconnected-(X2AK-1-Pad6)") (class "Default")
      (node (ref "X2") (pin "6") (pinfunction "1_6") (pintype "passive"))
    )
    (net (code "254") (name "unconnected-(X2AL-1-Pad7)") (class "Default")
      (node (ref "X2") (pin "7") (pinfunction "1_7") (pintype "passive"))
    )
    (net (code "255") (name "unconnected-(X2AM-1-Pad8)") (class "Default")
      (node (ref "X2") (pin "8") (pinfunction "1_8") (pintype "passive"))
    )
    (net (code "256") (name "unconnected-(X2AN-1-Pad9)") (class "Default")
      (node (ref "X2") (pin "9") (pinfunction "1_9") (pintype "passive"))
    )
    (net (code "257") (name "unconnected-(X2B-1-Pad10)") (class "Default")
      (node (ref "X2") (pin "10") (pinfunction "1_10") (pintype "passive"))
    )
    (net (code "258") (name "unconnected-(X2C-1-Pad11)") (class "Default")
      (node (ref "X2") (pin "11") (pinfunction "1_11") (pintype "passive"))
    )
    (net (code "259") (name "unconnected-(X2D-1-Pad12)") (class "Default")
      (node (ref "X2") (pin "12") (pinfunction "1_12") (pintype "passive"))
    )
    (net (code "260") (name "unconnected-(X2E-1-Pad13)") (class "Default")
      (node (ref "X2") (pin "13") (pinfunction "1_13") (pintype "passive"))
    )
    (net (code "261") (name "unconnected-(X2F-1-Pad14)") (class "Default")
      (node (ref "X2") (pin "14") (pinfunction "1_14") (pintype "passive"))
    )
    (net (code "262") (name "unconnected-(X2G-1-Pad15)") (class "Default")
      (node (ref "X2") (pin "15") (pinfunction "1_15") (pintype "passive"))
    )
    (net (code "263") (name "unconnected-(X2H-1-Pad16)") (class "Default")
      (node (ref "X2") (pin "16") (pinfunction "1_16") (pintype "passive"))
    )
    (net (code "264") (name "unconnected-(X2I-1-Pad17)") (class "Default")
      (node (ref "X2") (pin "17") (pinfunction "1_17") (pintype "passive"))
    )
    (net (code "265") (name "unconnected-(X2J-1-Pad18)") (class "Default")
      (node (ref "X2") (pin "18") (pinfunction "1_18") (pintype "passive"))
    )
    (net (code "266") (name "unconnected-(X2K-1-Pad19)") (class "Default")
      (node (ref "X2") (pin "19") (pinfunction "1_19") (pintype "passive"))
    )
    (net (code "267") (name "unconnected-(X2L-1-Pad2)") (class "Default")
      (node (ref "X2") (pin "2") (pinfunction "1_2") (pintype "passive"))
    )
    (net (code "268") (name "unconnected-(X2M-1-Pad20)") (class "Default")
      (node (ref "X2") (pin "20") (pinfunction "1_20") (pintype "passive"))
    )
    (net (code "269") (name "unconnected-(X2N-1-Pad21)") (class "Default")
      (node (ref "X2") (pin "21") (pinfunction "1_21") (pintype "passive"))
    )
    (net (code "270") (name "unconnected-(X2O-1-Pad22)") (class "Default")
      (node (ref "X2") (pin "22") (pinfunction "1_22") (pintype "passive"))
    )
    (net (code "271") (name "unconnected-(X2P-1-Pad23)") (class "Default")
      (node (ref "X2") (pin "23") (pinfunction "1_23") (pintype "passive"))
    )
    (net (code "272") (name "unconnected-(X2Q-1-Pad24)") (class "Default")
      (node (ref "X2") (pin "24") (pinfunction "1_24") (pintype "passive"))
    )
    (net (code "273") (name "unconnected-(X2R-1-Pad25)") (class "Default")
      (node (ref "X2") (pin "25") (pinfunction "1_25") (pintype "passive"))
    )
    (net (code "274") (name "unconnected-(X2S-1-Pad26)") (class "Default")
      (node (ref "X2") (pin "26") (pinfunction "1_26") (pintype "passive"))
    )
    (net (code "275") (name "unconnected-(X2T-1-Pad27)") (class "Default")
      (node (ref "X2") (pin "27") (pinfunction "1_27") (pintype "passive"))
    )
    (net (code "276") (name "unconnected-(X2U-1-Pad28)") (class "Default")
      (node (ref "X2") (pin "28") (pinfunction "1_28") (pintype "passive"))
    )
    (net (code "277") (name "unconnected-(X2V-1-Pad29)") (class "Default")
      (node (ref "X2") (pin "29") (pinfunction "1_29") (pintype "passive"))
    )
    (net (code "278") (name "unconnected-(X2W-1-Pad3)") (class "Default")
      (node (ref "X2") (pin "3") (pinfunction "1_3") (pintype "passive"))
    )
    (net (code "279") (name "unconnected-(X2X-1-Pad30)") (class "Default")
      (node (ref "X2") (pin "30") (pinfunction "1_30") (pintype "passive"))
    )
    (net (code "280") (name "unconnected-(X2Y-1-Pad31)") (class "Default")
      (node (ref "X2") (pin "31") (pinfunction "1_31") (pintype "passive"))
    )
    (net (code "281") (name "unconnected-(X2Z-1-Pad32)") (class "Default")
      (node (ref "X2") (pin "32") (pinfunction "1_32") (pintype "passive"))
    )
  )
)
